# 11-DPLL-2.net
KiCad netlist of a schematic drawn in Altium Designer
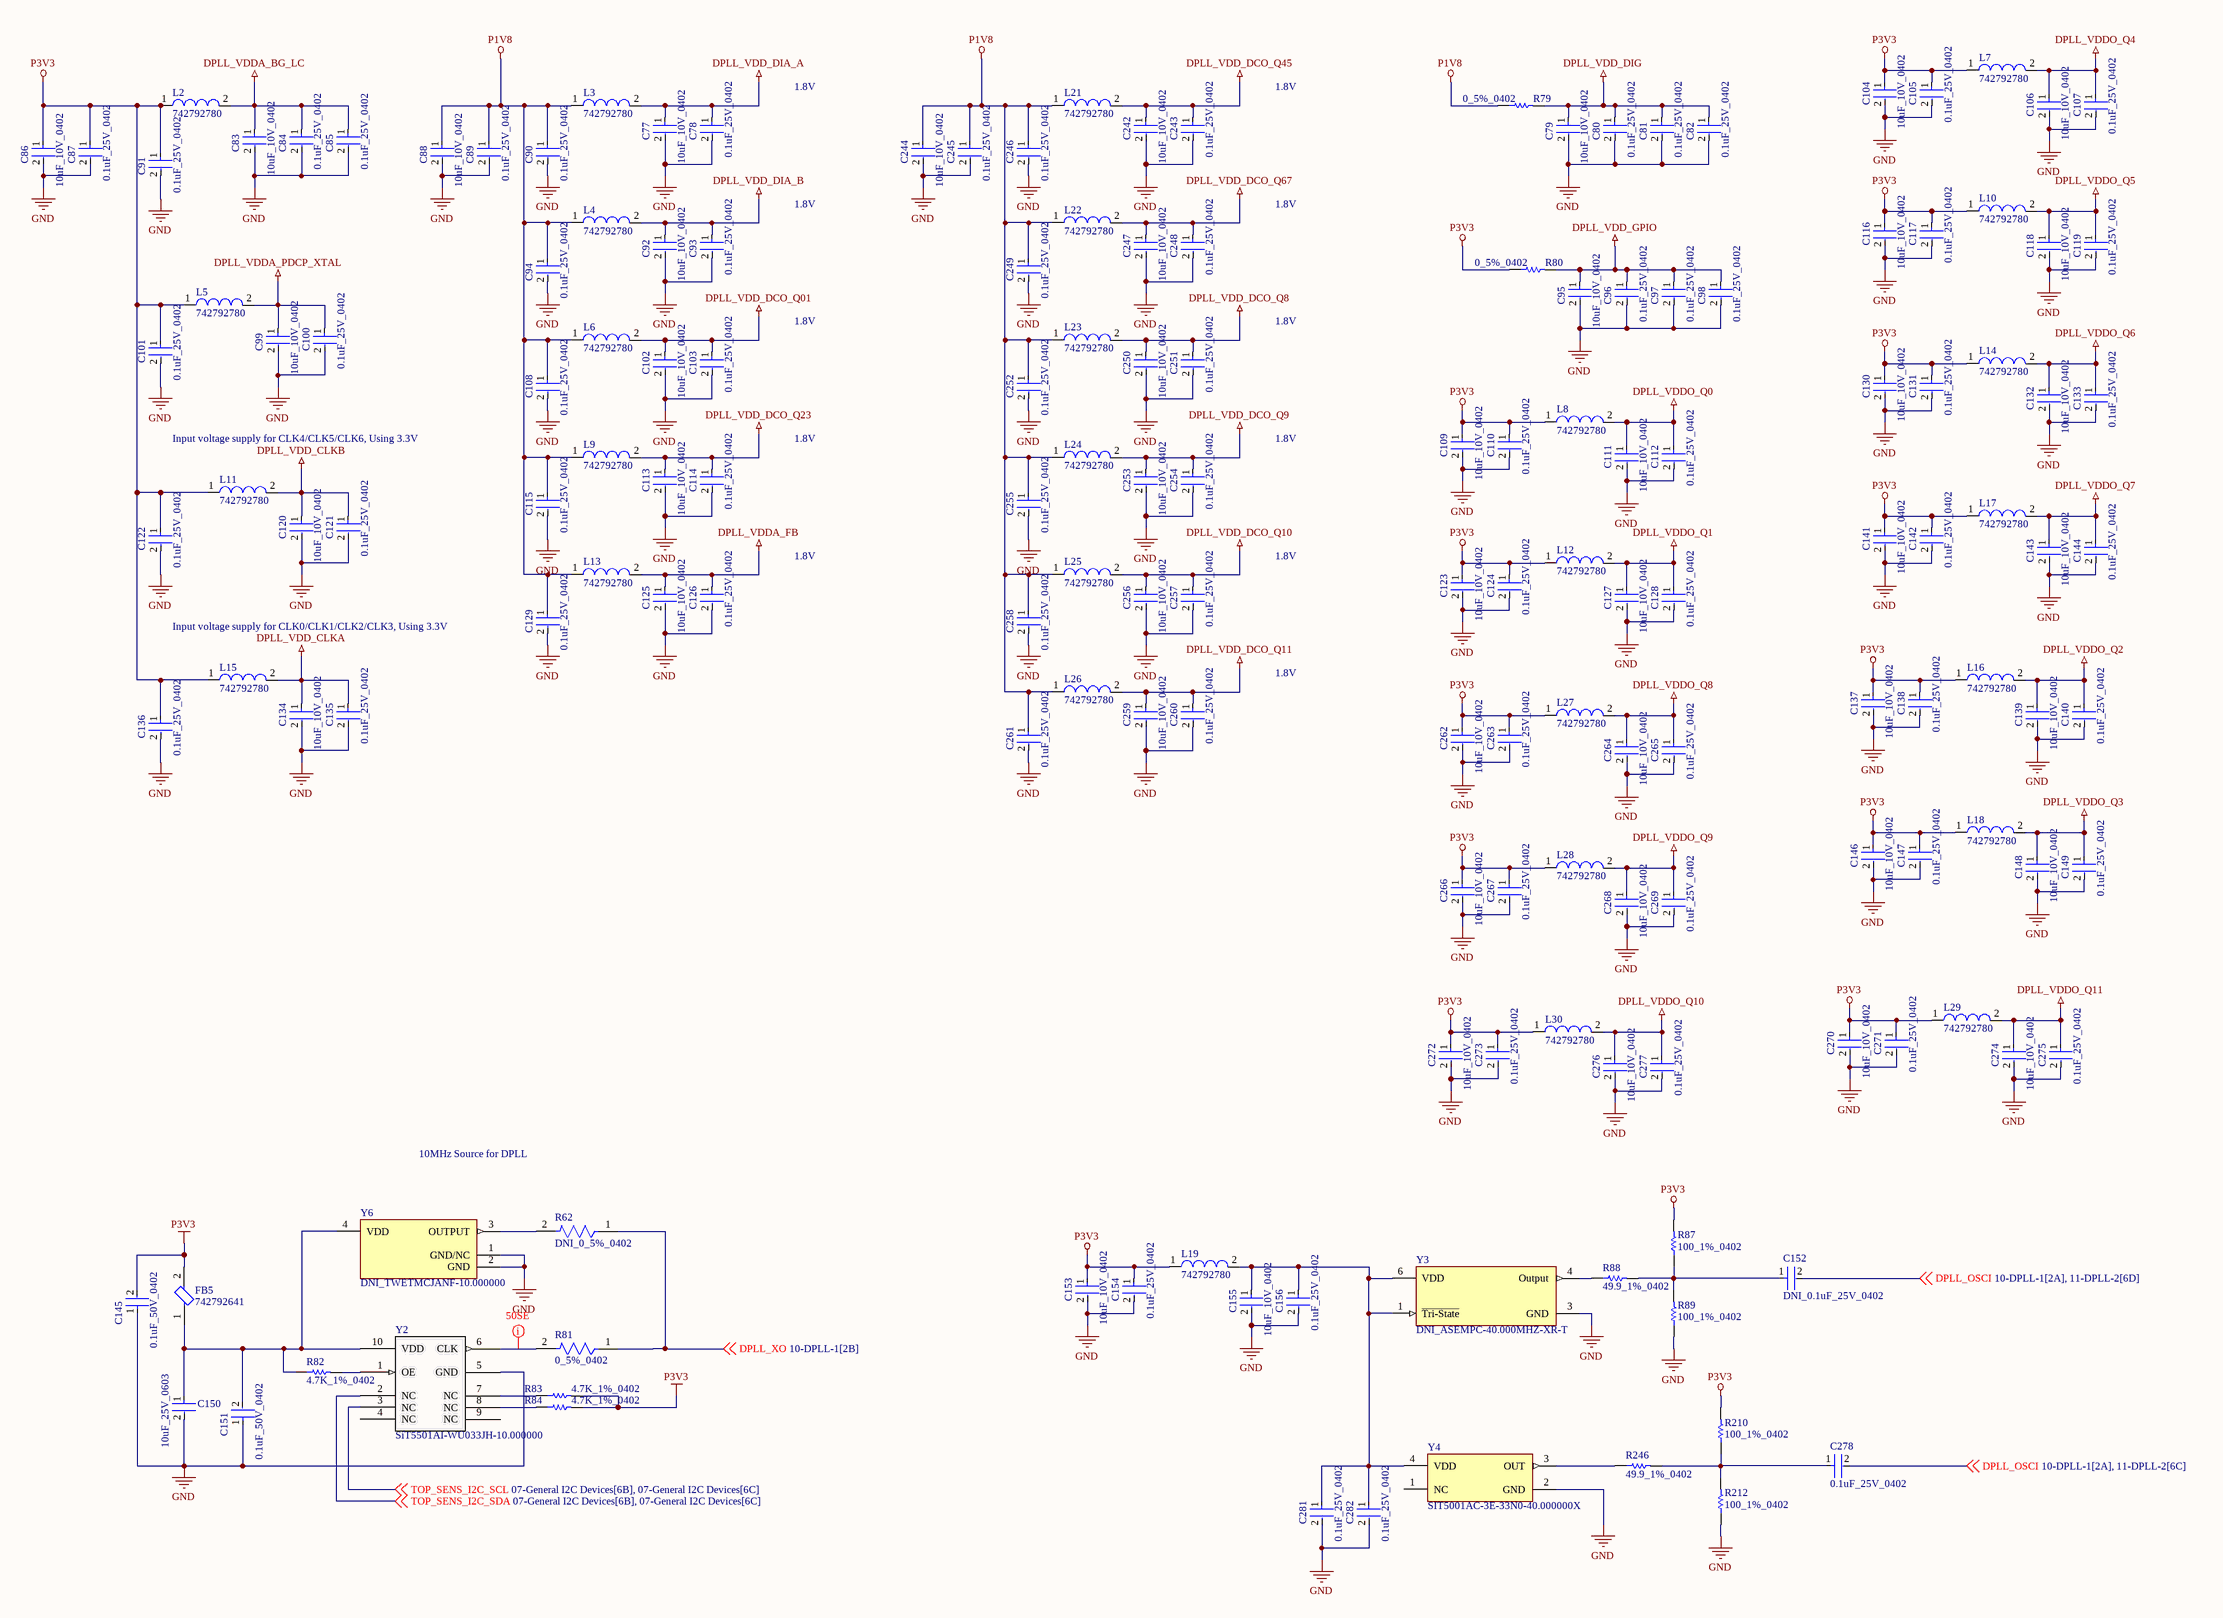
[diagram p0: 11-DPLL-2.SchDoc]

(export (version "E")
  (design (tool "Eeschema 10.0.6"))
  (components
    (comp (ref "C77")
      (value "10uF_10V_0402")
      (footprint "FP-CL05A106MP5NUNC-MFG")
      (description "CAP CER 10UF 10V X5R 0402")
      (fields
        (field (name "OCTOPART") "https://octopart.com/cl05a106mp5nunc-samsung-22457395")
        (field (name "TOLERANCE") "20%")
      )
      (libsource (lib "Altium Content Vault") (part "b4654b650e69147ec39a6b967a45e02"))
    )
    (comp (ref "C78")
      (value "0.1uF_25V_0402")
      (footprint "FP-0402-L_1_0_1-W_0_5_0_1-IPC_C")
      (description "General Purpose Ceramic Capacitor, 0402, 100nF, 10%, X7R, 15%, 25V")
      (fields (field (name "VOLTAGE") "25V") (field (name "TOLERANCE") "10%"))
      (libsource (lib "Altium Content Vault") (part "b4654b650e69147ec39a6b967a45e02"))
    )
    (comp (ref "C79")
      (value "10uF_10V_0402")
      (footprint "FP-CL05A106MP5NUNC-MFG")
      (description "CAP CER 10UF 10V X5R 0402")
      (fields
        (field (name "OCTOPART") "https://octopart.com/cl05a106mp5nunc-samsung-22457395")
        (field (name "TOLERANCE") "20%")
      )
      (libsource (lib "Altium Content Vault") (part "b4654b650e69147ec39a6b967a45e02"))
    )
    (comp (ref "C80")
      (value "0.1uF_25V_0402")
      (footprint "FP-0402-L_1_0_1-W_0_5_0_1-IPC_C")
      (description "General Purpose Ceramic Capacitor, 0402, 100nF, 10%, X7R, 15%, 25V")
      (fields (field (name "VOLTAGE") "25V") (field (name "TOLERANCE") "10%"))
      (libsource (lib "Altium Content Vault") (part "b4654b650e69147ec39a6b967a45e02"))
    )
    (comp (ref "C81")
      (value "0.1uF_25V_0402")
      (footprint "FP-0402-L_1_0_1-W_0_5_0_1-IPC_C")
      (description "General Purpose Ceramic Capacitor, 0402, 100nF, 10%, X7R, 15%, 25V")
      (fields (field (name "VOLTAGE") "25V") (field (name "TOLERANCE") "10%"))
      (libsource (lib "Altium Content Vault") (part "b4654b650e69147ec39a6b967a45e02"))
    )
    (comp (ref "C82")
      (value "0.1uF_25V_0402")
      (footprint "FP-0402-L_1_0_1-W_0_5_0_1-IPC_C")
      (description "General Purpose Ceramic Capacitor, 0402, 100nF, 10%, X7R, 15%, 25V")
      (fields (field (name "VOLTAGE") "25V") (field (name "TOLERANCE") "10%"))
      (libsource (lib "Altium Content Vault") (part "b4654b650e69147ec39a6b967a45e02"))
    )
    (comp (ref "C83")
      (value "10uF_10V_0402")
      (footprint "FP-CL05A106MP5NUNC-MFG")
      (description "CAP CER 10UF 10V X5R 0402")
      (fields
        (field (name "OCTOPART") "https://octopart.com/cl05a106mp5nunc-samsung-22457395")
        (field (name "TOLERANCE") "20%")
      )
      (libsource (lib "Altium Content Vault") (part "b4654b650e69147ec39a6b967a45e02"))
    )
    (comp (ref "C84")
      (value "0.1uF_25V_0402")
      (footprint "FP-0402-L_1_0_1-W_0_5_0_1-IPC_C")
      (description "General Purpose Ceramic Capacitor, 0402, 100nF, 10%, X7R, 15%, 25V")
      (fields (field (name "VOLTAGE") "25V") (field (name "TOLERANCE") "10%"))
      (libsource (lib "Altium Content Vault") (part "b4654b650e69147ec39a6b967a45e02"))
    )
    (comp (ref "C85")
      (value "0.1uF_25V_0402")
      (footprint "FP-0402-L_1_0_1-W_0_5_0_1-IPC_C")
      (description "General Purpose Ceramic Capacitor, 0402, 100nF, 10%, X7R, 15%, 25V")
      (fields (field (name "VOLTAGE") "25V") (field (name "TOLERANCE") "10%"))
      (libsource (lib "Altium Content Vault") (part "b4654b650e69147ec39a6b967a45e02"))
    )
    (comp (ref "C86")
      (value "10uF_10V_0402")
      (footprint "FP-CL05A106MP5NUNC-MFG")
      (description "CAP CER 10UF 10V X5R 0402")
      (fields
        (field (name "OCTOPART") "https://octopart.com/cl05a106mp5nunc-samsung-22457395")
        (field (name "TOLERANCE") "20%")
      )
      (libsource (lib "Altium Content Vault") (part "b4654b650e69147ec39a6b967a45e02"))
    )
    (comp (ref "C87")
      (value "0.1uF_25V_0402")
      (footprint "FP-0402-L_1_0_1-W_0_5_0_1-IPC_C")
      (description "General Purpose Ceramic Capacitor, 0402, 100nF, 10%, X7R, 15%, 25V")
      (fields (field (name "VOLTAGE") "25V") (field (name "TOLERANCE") "10%"))
      (libsource (lib "Altium Content Vault") (part "b4654b650e69147ec39a6b967a45e02"))
    )
    (comp (ref "C88")
      (value "10uF_10V_0402")
      (footprint "FP-CL05A106MP5NUNC-MFG")
      (description "CAP CER 10UF 10V X5R 0402")
      (fields
        (field (name "OCTOPART") "https://octopart.com/cl05a106mp5nunc-samsung-22457395")
        (field (name "TOLERANCE") "20%")
      )
      (libsource (lib "Altium Content Vault") (part "b4654b650e69147ec39a6b967a45e02"))
    )
    (comp (ref "C89")
      (value "0.1uF_25V_0402")
      (footprint "FP-0402-L_1_0_1-W_0_5_0_1-IPC_C")
      (description "General Purpose Ceramic Capacitor, 0402, 100nF, 10%, X7R, 15%, 25V")
      (fields (field (name "VOLTAGE") "25V") (field (name "TOLERANCE") "10%"))
      (libsource (lib "Altium Content Vault") (part "b4654b650e69147ec39a6b967a45e02"))
    )
    (comp (ref "C90")
      (value "0.1uF_25V_0402")
      (footprint "FP-0402-L_1_0_1-W_0_5_0_1-IPC_C")
      (description "General Purpose Ceramic Capacitor, 0402, 100nF, 10%, X7R, 15%, 25V")
      (fields (field (name "VOLTAGE") "25V") (field (name "TOLERANCE") "10%"))
      (libsource (lib "Altium Content Vault") (part "b4654b650e69147ec39a6b967a45e02"))
    )
    (comp (ref "C91")
      (value "0.1uF_25V_0402")
      (footprint "FP-0402-L_1_0_1-W_0_5_0_1-IPC_C")
      (description "General Purpose Ceramic Capacitor, 0402, 100nF, 10%, X7R, 15%, 25V")
      (fields (field (name "VOLTAGE") "25V") (field (name "TOLERANCE") "10%"))
      (libsource (lib "Altium Content Vault") (part "b4654b650e69147ec39a6b967a45e02"))
    )
    (comp (ref "C92")
      (value "10uF_10V_0402")
      (footprint "FP-CL05A106MP5NUNC-MFG")
      (description "CAP CER 10UF 10V X5R 0402")
      (fields
        (field (name "OCTOPART") "https://octopart.com/cl05a106mp5nunc-samsung-22457395")
        (field (name "TOLERANCE") "20%")
      )
      (libsource (lib "Altium Content Vault") (part "b4654b650e69147ec39a6b967a45e02"))
    )
    (comp (ref "C93")
      (value "0.1uF_25V_0402")
      (footprint "FP-0402-L_1_0_1-W_0_5_0_1-IPC_C")
      (description "General Purpose Ceramic Capacitor, 0402, 100nF, 10%, X7R, 15%, 25V")
      (fields (field (name "VOLTAGE") "25V") (field (name "TOLERANCE") "10%"))
      (libsource (lib "Altium Content Vault") (part "b4654b650e69147ec39a6b967a45e02"))
    )
    (comp (ref "C94")
      (value "0.1uF_25V_0402")
      (footprint "FP-0402-L_1_0_1-W_0_5_0_1-IPC_C")
      (description "General Purpose Ceramic Capacitor, 0402, 100nF, 10%, X7R, 15%, 25V")
      (fields (field (name "VOLTAGE") "25V") (field (name "TOLERANCE") "10%"))
      (libsource (lib "Altium Content Vault") (part "b4654b650e69147ec39a6b967a45e02"))
    )
    (comp (ref "C95")
      (value "10uF_10V_0402")
      (footprint "FP-CL05A106MP5NUNC-MFG")
      (description "CAP CER 10UF 10V X5R 0402")
      (fields
        (field (name "OCTOPART") "https://octopart.com/cl05a106mp5nunc-samsung-22457395")
        (field (name "TOLERANCE") "20%")
      )
      (libsource (lib "Altium Content Vault") (part "b4654b650e69147ec39a6b967a45e02"))
    )
    (comp (ref "C96")
      (value "0.1uF_25V_0402")
      (footprint "FP-0402-L_1_0_1-W_0_5_0_1-IPC_C")
      (description "General Purpose Ceramic Capacitor, 0402, 100nF, 10%, X7R, 15%, 25V")
      (fields (field (name "VOLTAGE") "25V") (field (name "TOLERANCE") "10%"))
      (libsource (lib "Altium Content Vault") (part "b4654b650e69147ec39a6b967a45e02"))
    )
    (comp (ref "C97")
      (value "0.1uF_25V_0402")
      (footprint "FP-0402-L_1_0_1-W_0_5_0_1-IPC_C")
      (description "General Purpose Ceramic Capacitor, 0402, 100nF, 10%, X7R, 15%, 25V")
      (fields (field (name "VOLTAGE") "25V") (field (name "TOLERANCE") "10%"))
      (libsource (lib "Altium Content Vault") (part "b4654b650e69147ec39a6b967a45e02"))
    )
    (comp (ref "C98")
      (value "0.1uF_25V_0402")
      (footprint "FP-0402-L_1_0_1-W_0_5_0_1-IPC_C")
      (description "General Purpose Ceramic Capacitor, 0402, 100nF, 10%, X7R, 15%, 25V")
      (fields (field (name "VOLTAGE") "25V") (field (name "TOLERANCE") "10%"))
      (libsource (lib "Altium Content Vault") (part "b4654b650e69147ec39a6b967a45e02"))
    )
    (comp (ref "C99")
      (value "10uF_10V_0402")
      (footprint "FP-CL05A106MP5NUNC-MFG")
      (description "CAP CER 10UF 10V X5R 0402")
      (fields
        (field (name "OCTOPART") "https://octopart.com/cl05a106mp5nunc-samsung-22457395")
        (field (name "TOLERANCE") "20%")
      )
      (libsource (lib "Altium Content Vault") (part "b4654b650e69147ec39a6b967a45e02"))
    )
    (comp (ref "C100")
      (value "0.1uF_25V_0402")
      (footprint "FP-0402-L_1_0_1-W_0_5_0_1-IPC_C")
      (description "General Purpose Ceramic Capacitor, 0402, 100nF, 10%, X7R, 15%, 25V")
      (fields (field (name "VOLTAGE") "25V") (field (name "TOLERANCE") "10%"))
      (libsource (lib "Altium Content Vault") (part "b4654b650e69147ec39a6b967a45e02"))
    )
    (comp (ref "C101")
      (value "0.1uF_25V_0402")
      (footprint "FP-0402-L_1_0_1-W_0_5_0_1-IPC_C")
      (description "General Purpose Ceramic Capacitor, 0402, 100nF, 10%, X7R, 15%, 25V")
      (fields (field (name "VOLTAGE") "25V") (field (name "TOLERANCE") "10%"))
      (libsource (lib "Altium Content Vault") (part "b4654b650e69147ec39a6b967a45e02"))
    )
    (comp (ref "C102")
      (value "10uF_10V_0402")
      (footprint "FP-CL05A106MP5NUNC-MFG")
      (description "CAP CER 10UF 10V X5R 0402")
      (fields
        (field (name "OCTOPART") "https://octopart.com/cl05a106mp5nunc-samsung-22457395")
        (field (name "TOLERANCE") "20%")
      )
      (libsource (lib "Altium Content Vault") (part "b4654b650e69147ec39a6b967a45e02"))
    )
    (comp (ref "C103")
      (value "0.1uF_25V_0402")
      (footprint "FP-0402-L_1_0_1-W_0_5_0_1-IPC_C")
      (description "General Purpose Ceramic Capacitor, 0402, 100nF, 10%, X7R, 15%, 25V")
      (fields (field (name "VOLTAGE") "25V") (field (name "TOLERANCE") "10%"))
      (libsource (lib "Altium Content Vault") (part "b4654b650e69147ec39a6b967a45e02"))
    )
    (comp (ref "C104")
      (value "10uF_10V_0402")
      (footprint "FP-CL05A106MP5NUNC-MFG")
      (description "CAP CER 10UF 10V X5R 0402")
      (fields
        (field (name "OCTOPART") "https://octopart.com/cl05a106mp5nunc-samsung-22457395")
        (field (name "TOLERANCE") "20%")
      )
      (libsource (lib "Altium Content Vault") (part "b4654b650e69147ec39a6b967a45e02"))
    )
    (comp (ref "C105")
      (value "0.1uF_25V_0402")
      (footprint "FP-0402-L_1_0_1-W_0_5_0_1-IPC_C")
      (description "General Purpose Ceramic Capacitor, 0402, 100nF, 10%, X7R, 15%, 25V")
      (fields (field (name "VOLTAGE") "25V") (field (name "TOLERANCE") "10%"))
      (libsource (lib "Altium Content Vault") (part "b4654b650e69147ec39a6b967a45e02"))
    )
    (comp (ref "C106")
      (value "10uF_10V_0402")
      (footprint "FP-CL05A106MP5NUNC-MFG")
      (description "CAP CER 10UF 10V X5R 0402")
      (fields
        (field (name "OCTOPART") "https://octopart.com/cl05a106mp5nunc-samsung-22457395")
        (field (name "TOLERANCE") "20%")
      )
      (libsource (lib "Altium Content Vault") (part "b4654b650e69147ec39a6b967a45e02"))
    )
    (comp (ref "C107")
      (value "0.1uF_25V_0402")
      (footprint "FP-0402-L_1_0_1-W_0_5_0_1-IPC_C")
      (description "General Purpose Ceramic Capacitor, 0402, 100nF, 10%, X7R, 15%, 25V")
      (fields (field (name "VOLTAGE") "25V") (field (name "TOLERANCE") "10%"))
      (libsource (lib "Altium Content Vault") (part "b4654b650e69147ec39a6b967a45e02"))
    )
    (comp (ref "C108")
      (value "0.1uF_25V_0402")
      (footprint "FP-0402-L_1_0_1-W_0_5_0_1-IPC_C")
      (description "General Purpose Ceramic Capacitor, 0402, 100nF, 10%, X7R, 15%, 25V")
      (fields (field (name "VOLTAGE") "25V") (field (name "TOLERANCE") "10%"))
      (libsource (lib "Altium Content Vault") (part "b4654b650e69147ec39a6b967a45e02"))
    )
    (comp (ref "C109")
      (value "10uF_10V_0402")
      (footprint "FP-CL05A106MP5NUNC-MFG")
      (description "CAP CER 10UF 10V X5R 0402")
      (fields
        (field (name "OCTOPART") "https://octopart.com/cl05a106mp5nunc-samsung-22457395")
        (field (name "TOLERANCE") "20%")
      )
      (libsource (lib "Altium Content Vault") (part "b4654b650e69147ec39a6b967a45e02"))
    )
    (comp (ref "C110")
      (value "0.1uF_25V_0402")
      (footprint "FP-0402-L_1_0_1-W_0_5_0_1-IPC_C")
      (description "General Purpose Ceramic Capacitor, 0402, 100nF, 10%, X7R, 15%, 25V")
      (fields (field (name "VOLTAGE") "25V") (field (name "TOLERANCE") "10%"))
      (libsource (lib "Altium Content Vault") (part "b4654b650e69147ec39a6b967a45e02"))
    )
    (comp (ref "C111")
      (value "10uF_10V_0402")
      (footprint "FP-CL05A106MP5NUNC-MFG")
      (description "CAP CER 10UF 10V X5R 0402")
      (fields
        (field (name "OCTOPART") "https://octopart.com/cl05a106mp5nunc-samsung-22457395")
        (field (name "TOLERANCE") "20%")
      )
      (libsource (lib "Altium Content Vault") (part "b4654b650e69147ec39a6b967a45e02"))
    )
    (comp (ref "C112")
      (value "0.1uF_25V_0402")
      (footprint "FP-0402-L_1_0_1-W_0_5_0_1-IPC_C")
      (description "General Purpose Ceramic Capacitor, 0402, 100nF, 10%, X7R, 15%, 25V")
      (fields (field (name "VOLTAGE") "25V") (field (name "TOLERANCE") "10%"))
      (libsource (lib "Altium Content Vault") (part "b4654b650e69147ec39a6b967a45e02"))
    )
    (comp (ref "C113")
      (value "10uF_10V_0402")
      (footprint "FP-CL05A106MP5NUNC-MFG")
      (description "CAP CER 10UF 10V X5R 0402")
      (fields
        (field (name "OCTOPART") "https://octopart.com/cl05a106mp5nunc-samsung-22457395")
        (field (name "TOLERANCE") "20%")
      )
      (libsource (lib "Altium Content Vault") (part "b4654b650e69147ec39a6b967a45e02"))
    )
    (comp (ref "C114")
      (value "0.1uF_25V_0402")
      (footprint "FP-0402-L_1_0_1-W_0_5_0_1-IPC_C")
      (description "General Purpose Ceramic Capacitor, 0402, 100nF, 10%, X7R, 15%, 25V")
      (fields (field (name "VOLTAGE") "25V") (field (name "TOLERANCE") "10%"))
      (libsource (lib "Altium Content Vault") (part "b4654b650e69147ec39a6b967a45e02"))
    )
    (comp (ref "C115")
      (value "0.1uF_25V_0402")
      (footprint "FP-0402-L_1_0_1-W_0_5_0_1-IPC_C")
      (description "General Purpose Ceramic Capacitor, 0402, 100nF, 10%, X7R, 15%, 25V")
      (fields (field (name "VOLTAGE") "25V") (field (name "TOLERANCE") "10%"))
      (libsource (lib "Altium Content Vault") (part "b4654b650e69147ec39a6b967a45e02"))
    )
    (comp (ref "C116")
      (value "10uF_10V_0402")
      (footprint "FP-CL05A106MP5NUNC-MFG")
      (description "CAP CER 10UF 10V X5R 0402")
      (fields
        (field (name "OCTOPART") "https://octopart.com/cl05a106mp5nunc-samsung-22457395")
        (field (name "TOLERANCE") "20%")
      )
      (libsource (lib "Altium Content Vault") (part "b4654b650e69147ec39a6b967a45e02"))
    )
    (comp (ref "C117")
      (value "0.1uF_25V_0402")
      (footprint "FP-0402-L_1_0_1-W_0_5_0_1-IPC_C")
      (description "General Purpose Ceramic Capacitor, 0402, 100nF, 10%, X7R, 15%, 25V")
      (fields (field (name "VOLTAGE") "25V") (field (name "TOLERANCE") "10%"))
      (libsource (lib "Altium Content Vault") (part "b4654b650e69147ec39a6b967a45e02"))
    )
    (comp (ref "C118")
      (value "10uF_10V_0402")
      (footprint "FP-CL05A106MP5NUNC-MFG")
      (description "CAP CER 10UF 10V X5R 0402")
      (fields
        (field (name "OCTOPART") "https://octopart.com/cl05a106mp5nunc-samsung-22457395")
        (field (name "TOLERANCE") "20%")
      )
      (libsource (lib "Altium Content Vault") (part "b4654b650e69147ec39a6b967a45e02"))
    )
    (comp (ref "C119")
      (value "0.1uF_25V_0402")
      (footprint "FP-0402-L_1_0_1-W_0_5_0_1-IPC_C")
      (description "General Purpose Ceramic Capacitor, 0402, 100nF, 10%, X7R, 15%, 25V")
      (fields (field (name "VOLTAGE") "25V") (field (name "TOLERANCE") "10%"))
      (libsource (lib "Altium Content Vault") (part "b4654b650e69147ec39a6b967a45e02"))
    )
    (comp (ref "C120")
      (value "10uF_10V_0402")
      (footprint "FP-CL05A106MP5NUNC-MFG")
      (description "CAP CER 10UF 10V X5R 0402")
      (fields
        (field (name "OCTOPART") "https://octopart.com/cl05a106mp5nunc-samsung-22457395")
        (field (name "TOLERANCE") "20%")
      )
      (libsource (lib "Altium Content Vault") (part "b4654b650e69147ec39a6b967a45e02"))
    )
    (comp (ref "C121")
      (value "0.1uF_25V_0402")
      (footprint "FP-0402-L_1_0_1-W_0_5_0_1-IPC_C")
      (description "General Purpose Ceramic Capacitor, 0402, 100nF, 10%, X7R, 15%, 25V")
      (fields (field (name "VOLTAGE") "25V") (field (name "TOLERANCE") "10%"))
      (libsource (lib "Altium Content Vault") (part "b4654b650e69147ec39a6b967a45e02"))
    )
    (comp (ref "C122")
      (value "0.1uF_25V_0402")
      (footprint "FP-0402-L_1_0_1-W_0_5_0_1-IPC_C")
      (description "General Purpose Ceramic Capacitor, 0402, 100nF, 10%, X7R, 15%, 25V")
      (fields (field (name "VOLTAGE") "25V") (field (name "TOLERANCE") "10%"))
      (libsource (lib "Altium Content Vault") (part "b4654b650e69147ec39a6b967a45e02"))
    )
    (comp (ref "C123")
      (value "10uF_10V_0402")
      (footprint "FP-CL05A106MP5NUNC-MFG")
      (description "CAP CER 10UF 10V X5R 0402")
      (fields
        (field (name "OCTOPART") "https://octopart.com/cl05a106mp5nunc-samsung-22457395")
        (field (name "TOLERANCE") "20%")
      )
      (libsource (lib "Altium Content Vault") (part "b4654b650e69147ec39a6b967a45e02"))
    )
    (comp (ref "C124")
      (value "0.1uF_25V_0402")
      (footprint "FP-0402-L_1_0_1-W_0_5_0_1-IPC_C")
      (description "General Purpose Ceramic Capacitor, 0402, 100nF, 10%, X7R, 15%, 25V")
      (fields (field (name "VOLTAGE") "25V") (field (name "TOLERANCE") "10%"))
      (libsource (lib "Altium Content Vault") (part "b4654b650e69147ec39a6b967a45e02"))
    )
    (comp (ref "C125")
      (value "10uF_10V_0402")
      (footprint "FP-CL05A106MP5NUNC-MFG")
      (description "CAP CER 10UF 10V X5R 0402")
      (fields
        (field (name "OCTOPART") "https://octopart.com/cl05a106mp5nunc-samsung-22457395")
        (field (name "TOLERANCE") "20%")
      )
      (libsource (lib "Altium Content Vault") (part "b4654b650e69147ec39a6b967a45e02"))
    )
    (comp (ref "C126")
      (value "0.1uF_25V_0402")
      (footprint "FP-0402-L_1_0_1-W_0_5_0_1-IPC_C")
      (description "General Purpose Ceramic Capacitor, 0402, 100nF, 10%, X7R, 15%, 25V")
      (fields (field (name "VOLTAGE") "25V") (field (name "TOLERANCE") "10%"))
      (libsource (lib "Altium Content Vault") (part "b4654b650e69147ec39a6b967a45e02"))
    )
    (comp (ref "C127")
      (value "10uF_10V_0402")
      (footprint "FP-CL05A106MP5NUNC-MFG")
      (description "CAP CER 10UF 10V X5R 0402")
      (fields
        (field (name "OCTOPART") "https://octopart.com/cl05a106mp5nunc-samsung-22457395")
        (field (name "TOLERANCE") "20%")
      )
      (libsource (lib "Altium Content Vault") (part "b4654b650e69147ec39a6b967a45e02"))
    )
    (comp (ref "C128")
      (value "0.1uF_25V_0402")
      (footprint "FP-0402-L_1_0_1-W_0_5_0_1-IPC_C")
      (description "General Purpose Ceramic Capacitor, 0402, 100nF, 10%, X7R, 15%, 25V")
      (fields (field (name "VOLTAGE") "25V") (field (name "TOLERANCE") "10%"))
      (libsource (lib "Altium Content Vault") (part "b4654b650e69147ec39a6b967a45e02"))
    )
    (comp (ref "C129")
      (value "0.1uF_25V_0402")
      (footprint "FP-0402-L_1_0_1-W_0_5_0_1-IPC_C")
      (description "General Purpose Ceramic Capacitor, 0402, 100nF, 10%, X7R, 15%, 25V")
      (fields (field (name "VOLTAGE") "25V") (field (name "TOLERANCE") "10%"))
      (libsource (lib "Altium Content Vault") (part "b4654b650e69147ec39a6b967a45e02"))
    )
    (comp (ref "C130")
      (value "10uF_10V_0402")
      (footprint "FP-CL05A106MP5NUNC-MFG")
      (description "CAP CER 10UF 10V X5R 0402")
      (fields
        (field (name "OCTOPART") "https://octopart.com/cl05a106mp5nunc-samsung-22457395")
        (field (name "TOLERANCE") "20%")
      )
      (libsource (lib "Altium Content Vault") (part "b4654b650e69147ec39a6b967a45e02"))
    )
    (comp (ref "C131")
      (value "0.1uF_25V_0402")
      (footprint "FP-0402-L_1_0_1-W_0_5_0_1-IPC_C")
      (description "General Purpose Ceramic Capacitor, 0402, 100nF, 10%, X7R, 15%, 25V")
      (fields (field (name "VOLTAGE") "25V") (field (name "TOLERANCE") "10%"))
      (libsource (lib "Altium Content Vault") (part "b4654b650e69147ec39a6b967a45e02"))
    )
    (comp (ref "C132")
      (value "10uF_10V_0402")
      (footprint "FP-CL05A106MP5NUNC-MFG")
      (description "CAP CER 10UF 10V X5R 0402")
      (fields
        (field (name "OCTOPART") "https://octopart.com/cl05a106mp5nunc-samsung-22457395")
        (field (name "TOLERANCE") "20%")
      )
      (libsource (lib "Altium Content Vault") (part "b4654b650e69147ec39a6b967a45e02"))
    )
    (comp (ref "C133")
      (value "0.1uF_25V_0402")
      (footprint "FP-0402-L_1_0_1-W_0_5_0_1-IPC_C")
      (description "General Purpose Ceramic Capacitor, 0402, 100nF, 10%, X7R, 15%, 25V")
      (fields (field (name "VOLTAGE") "25V") (field (name "TOLERANCE") "10%"))
      (libsource (lib "Altium Content Vault") (part "b4654b650e69147ec39a6b967a45e02"))
    )
    (comp (ref "C134")
      (value "10uF_10V_0402")
      (footprint "FP-CL05A106MP5NUNC-MFG")
      (description "CAP CER 10UF 10V X5R 0402")
      (fields
        (field (name "OCTOPART") "https://octopart.com/cl05a106mp5nunc-samsung-22457395")
        (field (name "TOLERANCE") "20%")
      )
      (libsource (lib "Altium Content Vault") (part "b4654b650e69147ec39a6b967a45e02"))
    )
    (comp (ref "C135")
      (value "0.1uF_25V_0402")
      (footprint "FP-0402-L_1_0_1-W_0_5_0_1-IPC_C")
      (description "General Purpose Ceramic Capacitor, 0402, 100nF, 10%, X7R, 15%, 25V")
      (fields (field (name "VOLTAGE") "25V") (field (name "TOLERANCE") "10%"))
      (libsource (lib "Altium Content Vault") (part "b4654b650e69147ec39a6b967a45e02"))
    )
    (comp (ref "C136")
      (value "0.1uF_25V_0402")
      (footprint "FP-0402-L_1_0_1-W_0_5_0_1-IPC_C")
      (description "General Purpose Ceramic Capacitor, 0402, 100nF, 10%, X7R, 15%, 25V")
      (fields (field (name "VOLTAGE") "25V") (field (name "TOLERANCE") "10%"))
      (libsource (lib "Altium Content Vault") (part "b4654b650e69147ec39a6b967a45e02"))
    )
    (comp (ref "C137")
      (value "10uF_10V_0402")
      (footprint "FP-CL05A106MP5NUNC-MFG")
      (description "CAP CER 10UF 10V X5R 0402")
      (fields
        (field (name "OCTOPART") "https://octopart.com/cl05a106mp5nunc-samsung-22457395")
        (field (name "TOLERANCE") "20%")
      )
      (libsource (lib "Altium Content Vault") (part "b4654b650e69147ec39a6b967a45e02"))
    )
    (comp (ref "C138")
      (value "0.1uF_25V_0402")
      (footprint "FP-0402-L_1_0_1-W_0_5_0_1-IPC_C")
      (description "General Purpose Ceramic Capacitor, 0402, 100nF, 10%, X7R, 15%, 25V")
      (fields (field (name "VOLTAGE") "25V") (field (name "TOLERANCE") "10%"))
      (libsource (lib "Altium Content Vault") (part "b4654b650e69147ec39a6b967a45e02"))
    )
    (comp (ref "C139")
      (value "10uF_10V_0402")
      (footprint "FP-CL05A106MP5NUNC-MFG")
      (description "CAP CER 10UF 10V X5R 0402")
      (fields
        (field (name "OCTOPART") "https://octopart.com/cl05a106mp5nunc-samsung-22457395")
        (field (name "TOLERANCE") "20%")
      )
      (libsource (lib "Altium Content Vault") (part "b4654b650e69147ec39a6b967a45e02"))
    )
    (comp (ref "C140")
      (value "0.1uF_25V_0402")
      (footprint "FP-0402-L_1_0_1-W_0_5_0_1-IPC_C")
      (description "General Purpose Ceramic Capacitor, 0402, 100nF, 10%, X7R, 15%, 25V")
      (fields (field (name "VOLTAGE") "25V") (field (name "TOLERANCE") "10%"))
      (libsource (lib "Altium Content Vault") (part "b4654b650e69147ec39a6b967a45e02"))
    )
    (comp (ref "C141")
      (value "10uF_10V_0402")
      (footprint "FP-CL05A106MP5NUNC-MFG")
      (description "CAP CER 10UF 10V X5R 0402")
      (fields
        (field (name "OCTOPART") "https://octopart.com/cl05a106mp5nunc-samsung-22457395")
        (field (name "TOLERANCE") "20%")
      )
      (libsource (lib "Altium Content Vault") (part "b4654b650e69147ec39a6b967a45e02"))
    )
    (comp (ref "C142")
      (value "0.1uF_25V_0402")
      (footprint "FP-0402-L_1_0_1-W_0_5_0_1-IPC_C")
      (description "General Purpose Ceramic Capacitor, 0402, 100nF, 10%, X7R, 15%, 25V")
      (fields (field (name "VOLTAGE") "25V") (field (name "TOLERANCE") "10%"))
      (libsource (lib "Altium Content Vault") (part "b4654b650e69147ec39a6b967a45e02"))
    )
    (comp (ref "C143")
      (value "10uF_10V_0402")
      (footprint "FP-CL05A106MP5NUNC-MFG")
      (description "CAP CER 10UF 10V X5R 0402")
      (fields
        (field (name "OCTOPART") "https://octopart.com/cl05a106mp5nunc-samsung-22457395")
        (field (name "TOLERANCE") "20%")
      )
      (libsource (lib "Altium Content Vault") (part "b4654b650e69147ec39a6b967a45e02"))
    )
    (comp (ref "C144")
      (value "0.1uF_25V_0402")
      (footprint "FP-0402-L_1_0_1-W_0_5_0_1-IPC_C")
      (description "General Purpose Ceramic Capacitor, 0402, 100nF, 10%, X7R, 15%, 25V")
      (fields (field (name "VOLTAGE") "25V") (field (name "TOLERANCE") "10%"))
      (libsource (lib "Altium Content Vault") (part "b4654b650e69147ec39a6b967a45e02"))
    )
    (comp (ref "C145")
      (value "0.1uF_50V_0402")
      (footprint "FP-C1005-050-0_05-IPC_C")
      (description "Multilayer Ceramic Capacitors 100nF ±10% 50V X7R SMD 0402")
      (fields (field (name "VOLTAGE") "50V") (field (name "TOLERANCE") "10%"))
      (libsource (lib "Altium Content Vault") (part "b4654b650e69147ec39a6b967a45e02"))
    )
    (comp (ref "C146")
      (value "10uF_10V_0402")
      (footprint "FP-CL05A106MP5NUNC-MFG")
      (description "CAP CER 10UF 10V X5R 0402")
      (fields
        (field (name "OCTOPART") "https://octopart.com/cl05a106mp5nunc-samsung-22457395")
        (field (name "TOLERANCE") "20%")
      )
      (libsource (lib "Altium Content Vault") (part "b4654b650e69147ec39a6b967a45e02"))
    )
    (comp (ref "C147")
      (value "0.1uF_25V_0402")
      (footprint "FP-0402-L_1_0_1-W_0_5_0_1-IPC_C")
      (description "General Purpose Ceramic Capacitor, 0402, 100nF, 10%, X7R, 15%, 25V")
      (fields (field (name "VOLTAGE") "25V") (field (name "TOLERANCE") "10%"))
      (libsource (lib "Altium Content Vault") (part "b4654b650e69147ec39a6b967a45e02"))
    )
    (comp (ref "C148")
      (value "10uF_10V_0402")
      (footprint "FP-CL05A106MP5NUNC-MFG")
      (description "CAP CER 10UF 10V X5R 0402")
      (fields
        (field (name "OCTOPART") "https://octopart.com/cl05a106mp5nunc-samsung-22457395")
        (field (name "TOLERANCE") "20%")
      )
      (libsource (lib "Altium Content Vault") (part "b4654b650e69147ec39a6b967a45e02"))
    )
    (comp (ref "C149")
      (value "0.1uF_25V_0402")
      (footprint "FP-0402-L_1_0_1-W_0_5_0_1-IPC_C")
      (description "General Purpose Ceramic Capacitor, 0402, 100nF, 10%, X7R, 15%, 25V")
      (fields (field (name "VOLTAGE") "25V") (field (name "TOLERANCE") "10%"))
      (libsource (lib "Altium Content Vault") (part "b4654b650e69147ec39a6b967a45e02"))
    )
    (comp (ref "C150")
      (value "10uF_25V_0603")
      (footprint "FP-CL10-IPC_C")
      (description "Cap Ceramic 10uF 25V X5R ±20% Pad SMD 0603 +85°C T/R")
      (fields (field (name "TOLERANCE") "20%"))
      (libsource (lib "Altium Content Vault") (part "b4654b650e69147ec39a6b967a45e02"))
    )
    (comp (ref "C151")
      (value "0.1uF_50V_0402")
      (footprint "FP-C1005-050-0_05-IPC_C")
      (description "Multilayer Ceramic Capacitors 100nF ±10% 50V X7R SMD 0402")
      (fields (field (name "VOLTAGE") "50V") (field (name "TOLERANCE") "10%"))
      (libsource (lib "Altium Content Vault") (part "b4654b650e69147ec39a6b967a45e02"))
    )
    (comp (ref "C152")
      (value "DNI_0.1uF_25V_0402")
      (footprint "FP-0402-L_1_0_1-W_0_5_0_1-IPC_C")
      (description "General Purpose Ceramic Capacitor, 0402, 100nF, 10%, X7R, 15%, 25V")
      (fields (field (name "VOLTAGE") "25V") (field (name "TOLERANCE") "10%"))
      (libsource (lib "Altium Content Vault") (part "b4654b650e69147ec39a6b967a45e02"))
    )
    (comp (ref "C153")
      (value "10uF_10V_0402")
      (footprint "FP-CL05A106MP5NUNC-MFG")
      (description "CAP CER 10UF 10V X5R 0402")
      (fields
        (field (name "OCTOPART") "https://octopart.com/cl05a106mp5nunc-samsung-22457395")
        (field (name "TOLERANCE") "20%")
      )
      (libsource (lib "Altium Content Vault") (part "b4654b650e69147ec39a6b967a45e02"))
    )
    (comp (ref "C154")
      (value "0.1uF_25V_0402")
      (footprint "FP-0402-L_1_0_1-W_0_5_0_1-IPC_C")
      (description "General Purpose Ceramic Capacitor, 0402, 100nF, 10%, X7R, 15%, 25V")
      (fields (field (name "VOLTAGE") "25V") (field (name "TOLERANCE") "10%"))
      (libsource (lib "Altium Content Vault") (part "b4654b650e69147ec39a6b967a45e02"))
    )
    (comp (ref "C155")
      (value "10uF_10V_0402")
      (footprint "FP-CL05A106MP5NUNC-MFG")
      (description "CAP CER 10UF 10V X5R 0402")
      (fields
        (field (name "OCTOPART") "https://octopart.com/cl05a106mp5nunc-samsung-22457395")
        (field (name "TOLERANCE") "20%")
      )
      (libsource (lib "Altium Content Vault") (part "b4654b650e69147ec39a6b967a45e02"))
    )
    (comp (ref "C156")
      (value "0.1uF_25V_0402")
      (footprint "FP-0402-L_1_0_1-W_0_5_0_1-IPC_C")
      (description "General Purpose Ceramic Capacitor, 0402, 100nF, 10%, X7R, 15%, 25V")
      (fields (field (name "VOLTAGE") "25V") (field (name "TOLERANCE") "10%"))
      (libsource (lib "Altium Content Vault") (part "b4654b650e69147ec39a6b967a45e02"))
    )
    (comp (ref "C242")
      (value "10uF_10V_0402")
      (footprint "FP-CL05A106MP5NUNC-MFG")
      (description "CAP CER 10UF 10V X5R 0402")
      (fields
        (field (name "OCTOPART") "https://octopart.com/cl05a106mp5nunc-samsung-22457395")
        (field (name "TOLERANCE") "20%")
      )
      (libsource (lib "Altium Content Vault") (part "b4654b650e69147ec39a6b967a45e02"))
    )
    (comp (ref "C243")
      (value "0.1uF_25V_0402")
      (footprint "FP-0402-L_1_0_1-W_0_5_0_1-IPC_C")
      (description "General Purpose Ceramic Capacitor, 0402, 100nF, 10%, X7R, 15%, 25V")
      (fields (field (name "VOLTAGE") "25V") (field (name "TOLERANCE") "10%"))
      (libsource (lib "Altium Content Vault") (part "b4654b650e69147ec39a6b967a45e02"))
    )
    (comp (ref "C244")
      (value "10uF_10V_0402")
      (footprint "FP-CL05A106MP5NUNC-MFG")
      (description "CAP CER 10UF 10V X5R 0402")
      (fields
        (field (name "OCTOPART") "https://octopart.com/cl05a106mp5nunc-samsung-22457395")
        (field (name "TOLERANCE") "20%")
      )
      (libsource (lib "Altium Content Vault") (part "b4654b650e69147ec39a6b967a45e02"))
    )
    (comp (ref "C245")
      (value "0.1uF_25V_0402")
      (footprint "FP-0402-L_1_0_1-W_0_5_0_1-IPC_C")
      (description "General Purpose Ceramic Capacitor, 0402, 100nF, 10%, X7R, 15%, 25V")
      (fields (field (name "VOLTAGE") "25V") (field (name "TOLERANCE") "10%"))
      (libsource (lib "Altium Content Vault") (part "b4654b650e69147ec39a6b967a45e02"))
    )
    (comp (ref "C246")
      (value "0.1uF_25V_0402")
      (footprint "FP-0402-L_1_0_1-W_0_5_0_1-IPC_C")
      (description "General Purpose Ceramic Capacitor, 0402, 100nF, 10%, X7R, 15%, 25V")
      (fields (field (name "VOLTAGE") "25V") (field (name "TOLERANCE") "10%"))
      (libsource (lib "Altium Content Vault") (part "b4654b650e69147ec39a6b967a45e02"))
    )
    (comp (ref "C247")
      (value "10uF_10V_0402")
      (footprint "FP-CL05A106MP5NUNC-MFG")
      (description "CAP CER 10UF 10V X5R 0402")
      (fields
        (field (name "OCTOPART") "https://octopart.com/cl05a106mp5nunc-samsung-22457395")
        (field (name "TOLERANCE") "20%")
      )
      (libsource (lib "Altium Content Vault") (part "b4654b650e69147ec39a6b967a45e02"))
    )
    (comp (ref "C248")
      (value "0.1uF_25V_0402")
      (footprint "FP-0402-L_1_0_1-W_0_5_0_1-IPC_C")
      (description "General Purpose Ceramic Capacitor, 0402, 100nF, 10%, X7R, 15%, 25V")
      (fields (field (name "VOLTAGE") "25V") (field (name "TOLERANCE") "10%"))
      (libsource (lib "Altium Content Vault") (part "b4654b650e69147ec39a6b967a45e02"))
    )
    (comp (ref "C249")
      (value "0.1uF_25V_0402")
      (footprint "FP-0402-L_1_0_1-W_0_5_0_1-IPC_C")
      (description "General Purpose Ceramic Capacitor, 0402, 100nF, 10%, X7R, 15%, 25V")
      (fields (field (name "VOLTAGE") "25V") (field (name "TOLERANCE") "10%"))
      (libsource (lib "Altium Content Vault") (part "b4654b650e69147ec39a6b967a45e02"))
    )
    (comp (ref "C250")
      (value "10uF_10V_0402")
      (footprint "FP-CL05A106MP5NUNC-MFG")
      (description "CAP CER 10UF 10V X5R 0402")
      (fields
        (field (name "OCTOPART") "https://octopart.com/cl05a106mp5nunc-samsung-22457395")
        (field (name "TOLERANCE") "20%")
      )
      (libsource (lib "Altium Content Vault") (part "b4654b650e69147ec39a6b967a45e02"))
    )
    (comp (ref "C251")
      (value "0.1uF_25V_0402")
      (footprint "FP-0402-L_1_0_1-W_0_5_0_1-IPC_C")
      (description "General Purpose Ceramic Capacitor, 0402, 100nF, 10%, X7R, 15%, 25V")
      (fields (field (name "VOLTAGE") "25V") (field (name "TOLERANCE") "10%"))
      (libsource (lib "Altium Content Vault") (part "b4654b650e69147ec39a6b967a45e02"))
    )
    (comp (ref "C252")
      (value "0.1uF_25V_0402")
      (footprint "FP-0402-L_1_0_1-W_0_5_0_1-IPC_C")
      (description "General Purpose Ceramic Capacitor, 0402, 100nF, 10%, X7R, 15%, 25V")
      (fields (field (name "VOLTAGE") "25V") (field (name "TOLERANCE") "10%"))
      (libsource (lib "Altium Content Vault") (part "b4654b650e69147ec39a6b967a45e02"))
    )
    (comp (ref "C253")
      (value "10uF_10V_0402")
      (footprint "FP-CL05A106MP5NUNC-MFG")
      (description "CAP CER 10UF 10V X5R 0402")
      (fields
        (field (name "OCTOPART") "https://octopart.com/cl05a106mp5nunc-samsung-22457395")
        (field (name "TOLERANCE") "20%")
      )
      (libsource (lib "Altium Content Vault") (part "b4654b650e69147ec39a6b967a45e02"))
    )
    (comp (ref "C254")
      (value "0.1uF_25V_0402")
      (footprint "FP-0402-L_1_0_1-W_0_5_0_1-IPC_C")
      (description "General Purpose Ceramic Capacitor, 0402, 100nF, 10%, X7R, 15%, 25V")
      (fields (field (name "VOLTAGE") "25V") (field (name "TOLERANCE") "10%"))
      (libsource (lib "Altium Content Vault") (part "b4654b650e69147ec39a6b967a45e02"))
    )
    (comp (ref "C255")
      (value "0.1uF_25V_0402")
      (footprint "FP-0402-L_1_0_1-W_0_5_0_1-IPC_C")
      (description "General Purpose Ceramic Capacitor, 0402, 100nF, 10%, X7R, 15%, 25V")
      (fields (field (name "VOLTAGE") "25V") (field (name "TOLERANCE") "10%"))
      (libsource (lib "Altium Content Vault") (part "b4654b650e69147ec39a6b967a45e02"))
    )
    (comp (ref "C256")
      (value "10uF_10V_0402")
      (footprint "FP-CL05A106MP5NUNC-MFG")
      (description "CAP CER 10UF 10V X5R 0402")
      (fields
        (field (name "OCTOPART") "https://octopart.com/cl05a106mp5nunc-samsung-22457395")
        (field (name "TOLERANCE") "20%")
      )
      (libsource (lib "Altium Content Vault") (part "b4654b650e69147ec39a6b967a45e02"))
    )
    (comp (ref "C257")
      (value "0.1uF_25V_0402")
      (footprint "FP-0402-L_1_0_1-W_0_5_0_1-IPC_C")
      (description "General Purpose Ceramic Capacitor, 0402, 100nF, 10%, X7R, 15%, 25V")
      (fields (field (name "VOLTAGE") "25V") (field (name "TOLERANCE") "10%"))
      (libsource (lib "Altium Content Vault") (part "b4654b650e69147ec39a6b967a45e02"))
    )
    (comp (ref "C258")
      (value "0.1uF_25V_0402")
      (footprint "FP-0402-L_1_0_1-W_0_5_0_1-IPC_C")
      (description "General Purpose Ceramic Capacitor, 0402, 100nF, 10%, X7R, 15%, 25V")
      (fields (field (name "VOLTAGE") "25V") (field (name "TOLERANCE") "10%"))
      (libsource (lib "Altium Content Vault") (part "b4654b650e69147ec39a6b967a45e02"))
    )
    (comp (ref "C259")
      (value "10uF_10V_0402")
      (footprint "FP-CL05A106MP5NUNC-MFG")
      (description "CAP CER 10UF 10V X5R 0402")
      (fields
        (field (name "OCTOPART") "https://octopart.com/cl05a106mp5nunc-samsung-22457395")
        (field (name "TOLERANCE") "20%")
      )
      (libsource (lib "Altium Content Vault") (part "b4654b650e69147ec39a6b967a45e02"))
    )
    (comp (ref "C260")
      (value "0.1uF_25V_0402")
      (footprint "FP-0402-L_1_0_1-W_0_5_0_1-IPC_C")
      (description "General Purpose Ceramic Capacitor, 0402, 100nF, 10%, X7R, 15%, 25V")
      (fields (field (name "VOLTAGE") "25V") (field (name "TOLERANCE") "10%"))
      (libsource (lib "Altium Content Vault") (part "b4654b650e69147ec39a6b967a45e02"))
    )
    (comp (ref "C261")
      (value "0.1uF_25V_0402")
      (footprint "FP-0402-L_1_0_1-W_0_5_0_1-IPC_C")
      (description "General Purpose Ceramic Capacitor, 0402, 100nF, 10%, X7R, 15%, 25V")
      (fields (field (name "VOLTAGE") "25V") (field (name "TOLERANCE") "10%"))
      (libsource (lib "Altium Content Vault") (part "b4654b650e69147ec39a6b967a45e02"))
    )
    (comp (ref "C262")
      (value "10uF_10V_0402")
      (footprint "FP-CL05A106MP5NUNC-MFG")
      (description "CAP CER 10UF 10V X5R 0402")
      (fields
        (field (name "OCTOPART") "https://octopart.com/cl05a106mp5nunc-samsung-22457395")
        (field (name "TOLERANCE") "20%")
      )
      (libsource (lib "Altium Content Vault") (part "b4654b650e69147ec39a6b967a45e02"))
    )
    (comp (ref "C263")
      (value "0.1uF_25V_0402")
      (footprint "FP-0402-L_1_0_1-W_0_5_0_1-IPC_C")
      (description "General Purpose Ceramic Capacitor, 0402, 100nF, 10%, X7R, 15%, 25V")
      (fields (field (name "VOLTAGE") "25V") (field (name "TOLERANCE") "10%"))
      (libsource (lib "Altium Content Vault") (part "b4654b650e69147ec39a6b967a45e02"))
    )
    (comp (ref "C264")
      (value "10uF_10V_0402")
      (footprint "FP-CL05A106MP5NUNC-MFG")
      (description "CAP CER 10UF 10V X5R 0402")
      (fields
        (field (name "OCTOPART") "https://octopart.com/cl05a106mp5nunc-samsung-22457395")
        (field (name "TOLERANCE") "20%")
      )
      (libsource (lib "Altium Content Vault") (part "b4654b650e69147ec39a6b967a45e02"))
    )
    (comp (ref "C265")
      (value "0.1uF_25V_0402")
      (footprint "FP-0402-L_1_0_1-W_0_5_0_1-IPC_C")
      (description "General Purpose Ceramic Capacitor, 0402, 100nF, 10%, X7R, 15%, 25V")
      (fields (field (name "VOLTAGE") "25V") (field (name "TOLERANCE") "10%"))
      (libsource (lib "Altium Content Vault") (part "b4654b650e69147ec39a6b967a45e02"))
    )
    (comp (ref "C266")
      (value "10uF_10V_0402")
      (footprint "FP-CL05A106MP5NUNC-MFG")
      (description "CAP CER 10UF 10V X5R 0402")
      (fields
        (field (name "OCTOPART") "https://octopart.com/cl05a106mp5nunc-samsung-22457395")
        (field (name "TOLERANCE") "20%")
      )
      (libsource (lib "Altium Content Vault") (part "b4654b650e69147ec39a6b967a45e02"))
    )
    (comp (ref "C267")
      (value "0.1uF_25V_0402")
      (footprint "FP-0402-L_1_0_1-W_0_5_0_1-IPC_C")
      (description "General Purpose Ceramic Capacitor, 0402, 100nF, 10%, X7R, 15%, 25V")
      (fields (field (name "VOLTAGE") "25V") (field (name "TOLERANCE") "10%"))
      (libsource (lib "Altium Content Vault") (part "b4654b650e69147ec39a6b967a45e02"))
    )
    (comp (ref "C268")
      (value "10uF_10V_0402")
      (footprint "FP-CL05A106MP5NUNC-MFG")
      (description "CAP CER 10UF 10V X5R 0402")
      (fields
        (field (name "OCTOPART") "https://octopart.com/cl05a106mp5nunc-samsung-22457395")
        (field (name "TOLERANCE") "20%")
      )
      (libsource (lib "Altium Content Vault") (part "b4654b650e69147ec39a6b967a45e02"))
    )
    (comp (ref "C269")
      (value "0.1uF_25V_0402")
      (footprint "FP-0402-L_1_0_1-W_0_5_0_1-IPC_C")
      (description "General Purpose Ceramic Capacitor, 0402, 100nF, 10%, X7R, 15%, 25V")
      (fields (field (name "VOLTAGE") "25V") (field (name "TOLERANCE") "10%"))
      (libsource (lib "Altium Content Vault") (part "b4654b650e69147ec39a6b967a45e02"))
    )
    (comp (ref "C270")
      (value "10uF_10V_0402")
      (footprint "FP-CL05A106MP5NUNC-MFG")
      (description "CAP CER 10UF 10V X5R 0402")
      (fields
        (field (name "OCTOPART") "https://octopart.com/cl05a106mp5nunc-samsung-22457395")
        (field (name "TOLERANCE") "20%")
      )
      (libsource (lib "Altium Content Vault") (part "b4654b650e69147ec39a6b967a45e02"))
    )
    (comp (ref "C271")
      (value "0.1uF_25V_0402")
      (footprint "FP-0402-L_1_0_1-W_0_5_0_1-IPC_C")
      (description "General Purpose Ceramic Capacitor, 0402, 100nF, 10%, X7R, 15%, 25V")
      (fields (field (name "VOLTAGE") "25V") (field (name "TOLERANCE") "10%"))
      (libsource (lib "Altium Content Vault") (part "b4654b650e69147ec39a6b967a45e02"))
    )
    (comp (ref "C272")
      (value "10uF_10V_0402")
      (footprint "FP-CL05A106MP5NUNC-MFG")
      (description "CAP CER 10UF 10V X5R 0402")
      (fields
        (field (name "OCTOPART") "https://octopart.com/cl05a106mp5nunc-samsung-22457395")
        (field (name "TOLERANCE") "20%")
      )
      (libsource (lib "Altium Content Vault") (part "b4654b650e69147ec39a6b967a45e02"))
    )
    (comp (ref "C273")
      (value "0.1uF_25V_0402")
      (footprint "FP-0402-L_1_0_1-W_0_5_0_1-IPC_C")
      (description "General Purpose Ceramic Capacitor, 0402, 100nF, 10%, X7R, 15%, 25V")
      (fields (field (name "VOLTAGE") "25V") (field (name "TOLERANCE") "10%"))
      (libsource (lib "Altium Content Vault") (part "b4654b650e69147ec39a6b967a45e02"))
    )
    (comp (ref "C274")
      (value "10uF_10V_0402")
      (footprint "FP-CL05A106MP5NUNC-MFG")
      (description "CAP CER 10UF 10V X5R 0402")
      (fields
        (field (name "OCTOPART") "https://octopart.com/cl05a106mp5nunc-samsung-22457395")
        (field (name "TOLERANCE") "20%")
      )
      (libsource (lib "Altium Content Vault") (part "b4654b650e69147ec39a6b967a45e02"))
    )
    (comp (ref "C275")
      (value "0.1uF_25V_0402")
      (footprint "FP-0402-L_1_0_1-W_0_5_0_1-IPC_C")
      (description "General Purpose Ceramic Capacitor, 0402, 100nF, 10%, X7R, 15%, 25V")
      (fields (field (name "VOLTAGE") "25V") (field (name "TOLERANCE") "10%"))
      (libsource (lib "Altium Content Vault") (part "b4654b650e69147ec39a6b967a45e02"))
    )
    (comp (ref "C276")
      (value "10uF_10V_0402")
      (footprint "FP-CL05A106MP5NUNC-MFG")
      (description "CAP CER 10UF 10V X5R 0402")
      (fields
        (field (name "OCTOPART") "https://octopart.com/cl05a106mp5nunc-samsung-22457395")
        (field (name "TOLERANCE") "20%")
      )
      (libsource (lib "Altium Content Vault") (part "b4654b650e69147ec39a6b967a45e02"))
    )
    (comp (ref "C277")
      (value "0.1uF_25V_0402")
      (footprint "FP-0402-L_1_0_1-W_0_5_0_1-IPC_C")
      (description "General Purpose Ceramic Capacitor, 0402, 100nF, 10%, X7R, 15%, 25V")
      (fields (field (name "VOLTAGE") "25V") (field (name "TOLERANCE") "10%"))
      (libsource (lib "Altium Content Vault") (part "b4654b650e69147ec39a6b967a45e02"))
    )
    (comp (ref "C278")
      (value "0.1uF_25V_0402")
      (footprint "FP-0402-L_1_0_1-W_0_5_0_1-IPC_C")
      (description "General Purpose Ceramic Capacitor, 0402, 100nF, 10%, X7R, 15%, 25V")
      (fields (field (name "VOLTAGE") "25V") (field (name "TOLERANCE") "10%"))
      (libsource (lib "Altium Content Vault") (part "b4654b650e69147ec39a6b967a45e02"))
    )
    (comp (ref "C281")
      (value "0.1uF_25V_0402")
      (footprint "FP-0402-L_1_0_1-W_0_5_0_1-IPC_C")
      (description "General Purpose Ceramic Capacitor, 0402, 100nF, 10%, X7R, 15%, 25V")
      (fields (field (name "VOLTAGE") "25V") (field (name "TOLERANCE") "10%"))
      (libsource (lib "Altium Content Vault") (part "b4654b650e69147ec39a6b967a45e02"))
    )
    (comp (ref "C282")
      (value "0.1uF_25V_0402")
      (footprint "FP-0402-L_1_0_1-W_0_5_0_1-IPC_C")
      (description "General Purpose Ceramic Capacitor, 0402, 100nF, 10%, X7R, 15%, 25V")
      (fields (field (name "VOLTAGE") "25V") (field (name "TOLERANCE") "10%"))
      (libsource (lib "Altium Content Vault") (part "b4654b650e69147ec39a6b967a45e02"))
    )
    (comp (ref "FB5")
      (value "742792641")
      (footprint "FP-742792641-MFG")
      (description "FERRITE BEAD 300 OHM 0603 1LN")
      (fields (field (name "TOLERANCE") "25%"))
      (libsource (lib "Altium Content Vault") (part "5f30dd21d616792df468990f7003faa"))
    )
    (comp (ref "L2")
      (value "742792780")
      (footprint "SMD-0402")
      (description "SMD EMI Suppression Ferrite Bead WE-CBF, Z = 220 Ohm")
      (libsource (lib "Altium Content Vault") (part "PAS-IND-INDUCTOR-2"))
    )
    (comp (ref "L3")
      (value "742792780")
      (footprint "SMD-0402")
      (description "SMD EMI Suppression Ferrite Bead WE-CBF, Z = 220 Ohm")
      (libsource (lib "Altium Content Vault") (part "PAS-IND-INDUCTOR-2"))
    )
    (comp (ref "L4")
      (value "742792780")
      (footprint "SMD-0402")
      (description "SMD EMI Suppression Ferrite Bead WE-CBF, Z = 220 Ohm")
      (libsource (lib "Altium Content Vault") (part "PAS-IND-INDUCTOR-2"))
    )
    (comp (ref "L5")
      (value "742792780")
      (footprint "SMD-0402")
      (description "SMD EMI Suppression Ferrite Bead WE-CBF, Z = 220 Ohm")
      (libsource (lib "Altium Content Vault") (part "PAS-IND-INDUCTOR-2"))
    )
    (comp (ref "L6")
      (value "742792780")
      (footprint "SMD-0402")
      (description "SMD EMI Suppression Ferrite Bead WE-CBF, Z = 220 Ohm")
      (libsource (lib "Altium Content Vault") (part "PAS-IND-INDUCTOR-2"))
    )
    (comp (ref "L7")
      (value "742792780")
      (footprint "SMD-0402")
      (description "SMD EMI Suppression Ferrite Bead WE-CBF, Z = 220 Ohm")
      (libsource (lib "Altium Content Vault") (part "PAS-IND-INDUCTOR-2"))
    )
    (comp (ref "L8")
      (value "742792780")
      (footprint "SMD-0402")
      (description "SMD EMI Suppression Ferrite Bead WE-CBF, Z = 220 Ohm")
      (libsource (lib "Altium Content Vault") (part "PAS-IND-INDUCTOR-2"))
    )
    (comp (ref "L9")
      (value "742792780")
      (footprint "SMD-0402")
      (description "SMD EMI Suppression Ferrite Bead WE-CBF, Z = 220 Ohm")
      (libsource (lib "Altium Content Vault") (part "PAS-IND-INDUCTOR-2"))
    )
    (comp (ref "L10")
      (value "742792780")
      (footprint "SMD-0402")
      (description "SMD EMI Suppression Ferrite Bead WE-CBF, Z = 220 Ohm")
      (libsource (lib "Altium Content Vault") (part "PAS-IND-INDUCTOR-2"))
    )
    (comp (ref "L11")
      (value "742792780")
      (footprint "SMD-0402")
      (description "SMD EMI Suppression Ferrite Bead WE-CBF, Z = 220 Ohm")
      (libsource (lib "Altium Content Vault") (part "PAS-IND-INDUCTOR-2"))
    )
    (comp (ref "L12")
      (value "742792780")
      (footprint "SMD-0402")
      (description "SMD EMI Suppression Ferrite Bead WE-CBF, Z = 220 Ohm")
      (libsource (lib "Altium Content Vault") (part "PAS-IND-INDUCTOR-2"))
    )
    (comp (ref "L13")
      (value "742792780")
      (footprint "SMD-0402")
      (description "SMD EMI Suppression Ferrite Bead WE-CBF, Z = 220 Ohm")
      (libsource (lib "Altium Content Vault") (part "PAS-IND-INDUCTOR-2"))
    )
    (comp (ref "L14")
      (value "742792780")
      (footprint "SMD-0402")
      (description "SMD EMI Suppression Ferrite Bead WE-CBF, Z = 220 Ohm")
      (libsource (lib "Altium Content Vault") (part "PAS-IND-INDUCTOR-2"))
    )
    (comp (ref "L15")
      (value "742792780")
      (footprint "SMD-0402")
      (description "SMD EMI Suppression Ferrite Bead WE-CBF, Z = 220 Ohm")
      (libsource (lib "Altium Content Vault") (part "PAS-IND-INDUCTOR-2"))
    )
    (comp (ref "L16")
      (value "742792780")
      (footprint "SMD-0402")
      (description "SMD EMI Suppression Ferrite Bead WE-CBF, Z = 220 Ohm")
      (libsource (lib "Altium Content Vault") (part "PAS-IND-INDUCTOR-2"))
    )
    (comp (ref "L17")
      (value "742792780")
      (footprint "SMD-0402")
      (description "SMD EMI Suppression Ferrite Bead WE-CBF, Z = 220 Ohm")
      (libsource (lib "Altium Content Vault") (part "PAS-IND-INDUCTOR-2"))
    )
    (comp (ref "L18")
      (value "742792780")
      (footprint "SMD-0402")
      (description "SMD EMI Suppression Ferrite Bead WE-CBF, Z = 220 Ohm")
      (libsource (lib "Altium Content Vault") (part "PAS-IND-INDUCTOR-2"))
    )
    (comp (ref "L19")
      (value "742792780")
      (footprint "SMD-0402")
      (description "SMD EMI Suppression Ferrite Bead WE-CBF, Z = 220 Ohm")
      (libsource (lib "Altium Content Vault") (part "PAS-IND-INDUCTOR-2"))
    )
    (comp (ref "L21")
      (value "742792780")
      (footprint "SMD-0402")
      (description "SMD EMI Suppression Ferrite Bead WE-CBF, Z = 220 Ohm")
      (libsource (lib "Altium Content Vault") (part "PAS-IND-INDUCTOR-2"))
    )
    (comp (ref "L22")
      (value "742792780")
      (footprint "SMD-0402")
      (description "SMD EMI Suppression Ferrite Bead WE-CBF, Z = 220 Ohm")
      (libsource (lib "Altium Content Vault") (part "PAS-IND-INDUCTOR-2"))
    )
    (comp (ref "L23")
      (value "742792780")
      (footprint "SMD-0402")
      (description "SMD EMI Suppression Ferrite Bead WE-CBF, Z = 220 Ohm")
      (libsource (lib "Altium Content Vault") (part "PAS-IND-INDUCTOR-2"))
    )
    (comp (ref "L24")
      (value "742792780")
      (footprint "SMD-0402")
      (description "SMD EMI Suppression Ferrite Bead WE-CBF, Z = 220 Ohm")
      (libsource (lib "Altium Content Vault") (part "PAS-IND-INDUCTOR-2"))
    )
    (comp (ref "L25")
      (value "742792780")
      (footprint "SMD-0402")
      (description "SMD EMI Suppression Ferrite Bead WE-CBF, Z = 220 Ohm")
      (libsource (lib "Altium Content Vault") (part "PAS-IND-INDUCTOR-2"))
    )
    (comp (ref "L26")
      (value "742792780")
      (footprint "SMD-0402")
      (description "SMD EMI Suppression Ferrite Bead WE-CBF, Z = 220 Ohm")
      (libsource (lib "Altium Content Vault") (part "PAS-IND-INDUCTOR-2"))
    )
    (comp (ref "L27")
      (value "742792780")
      (footprint "SMD-0402")
      (description "SMD EMI Suppression Ferrite Bead WE-CBF, Z = 220 Ohm")
      (libsource (lib "Altium Content Vault") (part "PAS-IND-INDUCTOR-2"))
    )
    (comp (ref "L28")
      (value "742792780")
      (footprint "SMD-0402")
      (description "SMD EMI Suppression Ferrite Bead WE-CBF, Z = 220 Ohm")
      (libsource (lib "Altium Content Vault") (part "PAS-IND-INDUCTOR-2"))
    )
    (comp (ref "L29")
      (value "742792780")
      (footprint "SMD-0402")
      (description "SMD EMI Suppression Ferrite Bead WE-CBF, Z = 220 Ohm")
      (libsource (lib "Altium Content Vault") (part "PAS-IND-INDUCTOR-2"))
    )
    (comp (ref "L30")
      (value "742792780")
      (footprint "SMD-0402")
      (description "SMD EMI Suppression Ferrite Bead WE-CBF, Z = 220 Ohm")
      (libsource (lib "Altium Content Vault") (part "PAS-IND-INDUCTOR-2"))
    )
    (comp (ref "R62")
      (value "DNI_0_5%_0402")
      (footprint "FP-AC0402-0_37-IPC_B")
      (description "RESISTOR 0402 JUMPER ZERO OHM")
      (fields (field (name "TOLERANCE") "1%"))
      (libsource (lib "Altium Content Vault") (part "1029c3af85768c4190bb7ad29bc67b5"))
    )
    (comp (ref "R79")
      (value "0_5%_0402")
      (footprint "RESC1005X40X25LL10T10")
      (fields (field (name "MANUFACTURER") "KOA Speer") (field (name "PART NUMBER") "RK73Z1ETTP"))
      (libsource (lib "Altium Content Vault") (part "RES"))
    )
    (comp (ref "R80")
      (value "0_5%_0402")
      (footprint "RESC1005X40X25LL10T10")
      (fields (field (name "MANUFACTURER") "KOA Speer") (field (name "PART NUMBER") "RK73Z1ETTP"))
      (libsource (lib "Altium Content Vault") (part "RES"))
    )
    (comp (ref "R81")
      (value "0_5%_0402")
      (footprint "FP-AC0402-0_37-IPC_B")
      (description "RESISTOR 0402 JUMPER ZERO OHM")
      (fields (field (name "TOLERANCE") "1%"))
      (libsource (lib "Altium Content Vault") (part "1029c3af85768c4190bb7ad29bc67b5"))
    )
    (comp (ref "R82")
      (value "4.7K_1%_0402")
      (footprint "RESC1005X40X25NL10T10")
      (fields (field (name "MANUFACTURER") "Bourns") (field (name "PART NUMBER") "CR0402-FX-4701GLF"))
      (libsource (lib "Altium Content Vault") (part "RES"))
    )
    (comp (ref "R83")
      (value "4.7K_1%_0402")
      (footprint "RESC1005X40X25NL10T10")
      (fields (field (name "MANUFACTURER") "Bourns") (field (name "PART NUMBER") "CR0402-FX-4701GLF"))
      (libsource (lib "Altium Content Vault") (part "RES"))
    )
    (comp (ref "R84")
      (value "4.7K_1%_0402")
      (footprint "RESC1005X40X25NL10T10")
      (fields (field (name "MANUFACTURER") "Bourns") (field (name "PART NUMBER") "CR0402-FX-4701GLF"))
      (libsource (lib "Altium Content Vault") (part "RES"))
    )
    (comp (ref "R87")
      (value "100_1%_0402")
      (footprint "RESC1005X40X25ML05T10")
      (fields (field (name "PART NUMBER") "ERJ-U02F1000X") (field (name "MANUFACTURER") "Panasonic"))
      (libsource (lib "Altium Content Vault") (part "RES"))
    )
    (comp (ref "R88")
      (value "49.9_1%_0402")
      (footprint "RESC1005X40X25NL10T10")
      (fields (field (name "PART NUMBER") "RK73H1ETTP49R9F") (field (name "MANUFACTURER") "KOA Speer"))
      (libsource (lib "Altium Content Vault") (part "RES"))
    )
    (comp (ref "R89")
      (value "100_1%_0402")
      (footprint "RESC1005X40X25ML05T10")
      (fields (field (name "PART NUMBER") "ERJ-U02F1000X") (field (name "MANUFACTURER") "Panasonic"))
      (libsource (lib "Altium Content Vault") (part "RES"))
    )
    (comp (ref "R210")
      (value "100_1%_0402")
      (footprint "RESC1005X40X25ML05T10")
      (fields (field (name "PART NUMBER") "ERJ-U02F1000X") (field (name "MANUFACTURER") "Panasonic"))
      (libsource (lib "Altium Content Vault") (part "RES"))
    )
    (comp (ref "R212")
      (value "100_1%_0402")
      (footprint "RESC1005X40X25ML05T10")
      (fields (field (name "PART NUMBER") "ERJ-U02F1000X") (field (name "MANUFACTURER") "Panasonic"))
      (libsource (lib "Altium Content Vault") (part "RES"))
    )
    (comp (ref "R246")
      (value "49.9_1%_0402")
      (footprint "RESC1005X40X25NL10T10")
      (fields (field (name "PART NUMBER") "RK73H1ETTP49R9F") (field (name "MANUFACTURER") "KOA Speer"))
      (libsource (lib "Altium Content Vault") (part "RES"))
    )
    (comp (ref "Y2")
      (value "SiTime_SiT5501AC-WU-33E0-10T")
      (footprint "SITIME_SPL-086-CQFN-010-C07050_REV_DRAFT")
      (description "OSC, MEMS, STRATUM 3E, 10.000MHZ, 10PPB STAB, LVCMOS, 3.3V, O/P EN, 7.0X5.0X2.2MM, CQFN-10")
      (fields
        (field (name "MANUFACTURER PART NUMBER") "SiT5501AI-WU033JH-10.000000")
        (field (name "MANUFACTURER") "SiTime")
      )
      (libsource (lib "OCXO_DaughterCard") (part "CMP-OSC-00029-2"))
    )
    (comp (ref "Y3")
      (value "DNI_ASEMPC-40.000MHZ-XR-T")
      (footprint "FP-ASEMP-CMOS-MFG")
      (description "MEMS Oscillator 40MHz ±25ppm CMOS 2.25V~3.6V 6-SMD 3.2mm x 2.5mm")
      (libsource (lib "Altium Content Vault") (part "9526c112e3a98a1af86e8f4e974a861"))
    )
    (comp (ref "Y4")
      (value "SIT5001AC-3E-33N0-40.000000X")
      (footprint "FP-SiT5001-3-MFG")
      (description "MEMS OSC TCXO 40.0000MHZ LVCMOS")
      (libsource (lib "Altium Content Vault") (part "f2b4964c30f19ad016f2c5313c7e3e3"))
    )
    (comp (ref "Y6")
      (value "DNI_TWETMCJANF-10.000000")
      (footprint "FP-TWETMCJANF-10_000000-MFG")
      (description "XTAL OSC TCXO 10.0000MHZ CMOS")
      (fields
        (field (name "MANUFACTURER PART NUMBER") "TWETMCJANF-10.000000")
        (field (name "OCTOPART") "https://octopart.com/twetmcjanf-10.000000-taitien-75080612")
      )
      (libsource (lib "Altium Content Vault") (part "cad4c3239b6ef19b17a0f879cedd8e8"))
    )
  )
  (nets
    (net (code "1") (name "DPLL_OSCI") (class "Default")
      (node (ref "C152") (pin "2") (pinfunction "2_2") (pintype "passive"))
      (node (ref "C278") (pin "2") (pinfunction "2_2") (pintype "passive"))
    )
    (net (code "2") (name "DPLL_VDDA_BG_LC") (class "Default")
      (node (ref "C83") (pin "1") (pinfunction "1_1") (pintype "passive"))
      (node (ref "C84") (pin "1") (pinfunction "1_1") (pintype "passive"))
      (node (ref "C85") (pin "1") (pinfunction "1_1") (pintype "passive"))
      (node (ref "L2") (pin "2") (pinfunction "2_2") (pintype "passive"))
    )
    (net (code "3") (name "DPLL_VDDA_FB") (class "Default")
      (node (ref "C125") (pin "1") (pinfunction "1_1") (pintype "passive"))
      (node (ref "C126") (pin "1") (pinfunction "1_1") (pintype "passive"))
      (node (ref "L13") (pin "2") (pinfunction "2_2") (pintype "passive"))
    )
    (net (code "4") (name "DPLL_VDDA_PDCP_XTAL") (class "Default")
      (node (ref "C100") (pin "1") (pinfunction "1_1") (pintype "passive"))
      (node (ref "C99") (pin "1") (pinfunction "1_1") (pintype "passive"))
      (node (ref "L5") (pin "2") (pinfunction "2_2") (pintype "passive"))
    )
    (net (code "5") (name "DPLL_VDDO_Q0") (class "Default")
      (node (ref "C111") (pin "1") (pinfunction "1_1") (pintype "passive"))
      (node (ref "C112") (pin "1") (pinfunction "1_1") (pintype "passive"))
      (node (ref "L8") (pin "2") (pinfunction "2_2") (pintype "passive"))
    )
    (net (code "6") (name "DPLL_VDDO_Q1") (class "Default")
      (node (ref "C127") (pin "1") (pinfunction "1_1") (pintype "passive"))
      (node (ref "C128") (pin "1") (pinfunction "1_1") (pintype "passive"))
      (node (ref "L12") (pin "2") (pinfunction "2_2") (pintype "passive"))
    )
    (net (code "7") (name "DPLL_VDDO_Q2") (class "Default")
      (node (ref "C139") (pin "1") (pinfunction "1_1") (pintype "passive"))
      (node (ref "C140") (pin "1") (pinfunction "1_1") (pintype "passive"))
      (node (ref "L16") (pin "2") (pinfunction "2_2") (pintype "passive"))
    )
    (net (code "8") (name "DPLL_VDDO_Q3") (class "Default")
      (node (ref "C148") (pin "1") (pinfunction "1_1") (pintype "passive"))
      (node (ref "C149") (pin "1") (pinfunction "1_1") (pintype "passive"))
      (node (ref "L18") (pin "2") (pinfunction "2_2") (pintype "passive"))
    )
    (net (code "9") (name "DPLL_VDDO_Q4") (class "Default")
      (node (ref "C106") (pin "1") (pinfunction "1_1") (pintype "passive"))
      (node (ref "C107") (pin "1") (pinfunction "1_1") (pintype "passive"))
      (node (ref "L7") (pin "2") (pinfunction "2_2") (pintype "passive"))
    )
    (net (code "10") (name "DPLL_VDDO_Q5") (class "Default")
      (node (ref "C118") (pin "1") (pinfunction "1_1") (pintype "passive"))
      (node (ref "C119") (pin "1") (pinfunction "1_1") (pintype "passive"))
      (node (ref "L10") (pin "2") (pinfunction "2_2") (pintype "passive"))
    )
    (net (code "11") (name "DPLL_VDDO_Q6") (class "Default")
      (node (ref "C132") (pin "1") (pinfunction "1_1") (pintype "passive"))
      (node (ref "C133") (pin "1") (pinfunction "1_1") (pintype "passive"))
      (node (ref "L14") (pin "2") (pinfunction "2_2") (pintype "passive"))
    )
    (net (code "12") (name "DPLL_VDDO_Q7") (class "Default")
      (node (ref "C143") (pin "1") (pinfunction "1_1") (pintype "passive"))
      (node (ref "C144") (pin "1") (pinfunction "1_1") (pintype "passive"))
      (node (ref "L17") (pin "2") (pinfunction "2_2") (pintype "passive"))
    )
    (net (code "13") (name "DPLL_VDDO_Q8") (class "Default")
      (node (ref "C264") (pin "1") (pinfunction "1_1") (pintype "passive"))
      (node (ref "C265") (pin "1") (pinfunction "1_1") (pintype "passive"))
      (node (ref "L27") (pin "2") (pinfunction "2_2") (pintype "passive"))
    )
    (net (code "14") (name "DPLL_VDDO_Q9") (class "Default")
      (node (ref "C268") (pin "1") (pinfunction "1_1") (pintype "passive"))
      (node (ref "C269") (pin "1") (pinfunction "1_1") (pintype "passive"))
      (node (ref "L28") (pin "2") (pinfunction "2_2") (pintype "passive"))
    )
    (net (code "15") (name "DPLL_VDDO_Q10") (class "Default")
      (node (ref "C276") (pin "1") (pinfunction "1_1") (pintype "passive"))
      (node (ref "C277") (pin "1") (pinfunction "1_1") (pintype "passive"))
      (node (ref "L30") (pin "2") (pinfunction "2_2") (pintype "passive"))
    )
    (net (code "16") (name "DPLL_VDDO_Q11") (class "Default")
      (node (ref "C274") (pin "1") (pinfunction "1_1") (pintype "passive"))
      (node (ref "C275") (pin "1") (pinfunction "1_1") (pintype "passive"))
      (node (ref "L29") (pin "2") (pinfunction "2_2") (pintype "passive"))
    )
    (net (code "17") (name "DPLL_VDD_CLKA") (class "Default")
      (node (ref "C134") (pin "1") (pinfunction "1_1") (pintype "passive"))
      (node (ref "C135") (pin "1") (pinfunction "1_1") (pintype "passive"))
      (node (ref "L15") (pin "2") (pinfunction "2_2") (pintype "passive"))
    )
    (net (code "18") (name "DPLL_VDD_CLKB") (class "Default")
      (node (ref "C120") (pin "1") (pinfunction "1_1") (pintype "passive"))
      (node (ref "C121") (pin "1") (pinfunction "1_1") (pintype "passive"))
      (node (ref "L11") (pin "2") (pinfunction "2_2") (pintype "passive"))
    )
    (net (code "19") (name "DPLL_VDD_DCO_Q01") (class "Default")
      (node (ref "C102") (pin "1") (pinfunction "1_1") (pintype "passive"))
      (node (ref "C103") (pin "1") (pinfunction "1_1") (pintype "passive"))
      (node (ref "L6") (pin "2") (pinfunction "2_2") (pintype "passive"))
    )
    (net (code "20") (name "DPLL_VDD_DCO_Q8") (class "Default")
      (node (ref "C250") (pin "1") (pinfunction "1_1") (pintype "passive"))
      (node (ref "C251") (pin "1") (pinfunction "1_1") (pintype "passive"))
      (node (ref "L23") (pin "2") (pinfunction "2_2") (pintype "passive"))
    )
    (net (code "21") (name "DPLL_VDD_DCO_Q9") (class "Default")
      (node (ref "C253") (pin "1") (pinfunction "1_1") (pintype "passive"))
      (node (ref "C254") (pin "1") (pinfunction "1_1") (pintype "passive"))
      (node (ref "L24") (pin "2") (pinfunction "2_2") (pintype "passive"))
    )
    (net (code "22") (name "DPLL_VDD_DCO_Q10") (class "Default")
      (node (ref "C256") (pin "1") (pinfunction "1_1") (pintype "passive"))
      (node (ref "C257") (pin "1") (pinfunction "1_1") (pintype "passive"))
      (node (ref "L25") (pin "2") (pinfunction "2_2") (pintype "passive"))
    )
    (net (code "23") (name "DPLL_VDD_DCO_Q11") (class "Default")
      (node (ref "C259") (pin "1") (pinfunction "1_1") (pintype "passive"))
      (node (ref "C260") (pin "1") (pinfunction "1_1") (pintype "passive"))
      (node (ref "L26") (pin "2") (pinfunction "2_2") (pintype "passive"))
    )
    (net (code "24") (name "DPLL_VDD_DCO_Q23") (class "Default")
      (node (ref "C113") (pin "1") (pinfunction "1_1") (pintype "passive"))
      (node (ref "C114") (pin "1") (pinfunction "1_1") (pintype "passive"))
      (node (ref "L9") (pin "2") (pinfunction "2_2") (pintype "passive"))
    )
    (net (code "25") (name "DPLL_VDD_DCO_Q45") (class "Default")
      (node (ref "C242") (pin "1") (pinfunction "1_1") (pintype "passive"))
      (node (ref "C243") (pin "1") (pinfunction "1_1") (pintype "passive"))
      (node (ref "L21") (pin "2") (pinfunction "2_2") (pintype "passive"))
    )
    (net (code "26") (name "DPLL_VDD_DCO_Q67") (class "Default")
      (node (ref "C247") (pin "1") (pinfunction "1_1") (pintype "passive"))
      (node (ref "C248") (pin "1") (pinfunction "1_1") (pintype "passive"))
      (node (ref "L22") (pin "2") (pinfunction "2_2") (pintype "passive"))
    )
    (net (code "27") (name "DPLL_VDD_DIA_A") (class "Default")
      (node (ref "C77") (pin "1") (pinfunction "1_1") (pintype "passive"))
      (node (ref "C78") (pin "1") (pinfunction "1_1") (pintype "passive"))
      (node (ref "L3") (pin "2") (pinfunction "2_2") (pintype "passive"))
    )
    (net (code "28") (name "DPLL_VDD_DIA_B") (class "Default")
      (node (ref "C92") (pin "1") (pinfunction "1_1") (pintype "passive"))
      (node (ref "C93") (pin "1") (pinfunction "1_1") (pintype "passive"))
      (node (ref "L4") (pin "2") (pinfunction "2_2") (pintype "passive"))
    )
    (net (code "29") (name "DPLL_VDD_DIG") (class "Default")
      (node (ref "C79") (pin "1") (pinfunction "1_1") (pintype "passive"))
      (node (ref "C80") (pin "1") (pinfunction "1_1") (pintype "passive"))
      (node (ref "C81") (pin "1") (pinfunction "1_1") (pintype "passive"))
      (node (ref "C82") (pin "1") (pinfunction "1_1") (pintype "passive"))
      (node (ref "R79") (pin "2") (pinfunction "2_2") (pintype "passive"))
    )
    (net (code "30") (name "DPLL_VDD_GPIO") (class "Default")
      (node (ref "C95") (pin "1") (pinfunction "1_1") (pintype "passive"))
      (node (ref "C96") (pin "1") (pinfunction "1_1") (pintype "passive"))
      (node (ref "C97") (pin "1") (pinfunction "1_1") (pintype "passive"))
      (node (ref "C98") (pin "1") (pinfunction "1_1") (pintype "passive"))
      (node (ref "R80") (pin "2") (pinfunction "2_2") (pintype "passive"))
    )
    (net (code "31") (name "DPLL_XO") (class "Default")
      (node (ref "R62") (pin "1") (pinfunction "1_1") (pintype "passive"))
      (node (ref "R81") (pin "1") (pinfunction "1_1") (pintype "passive"))
    )
    (net (code "32") (name "GND") (class "Default")
      (node (ref "C100") (pin "2") (pinfunction "2_2") (pintype "passive"))
      (node (ref "C101") (pin "2") (pinfunction "2_2") (pintype "passive"))
      (node (ref "C102") (pin "2") (pinfunction "2_2") (pintype "passive"))
      (node (ref "C103") (pin "2") (pinfunction "2_2") (pintype "passive"))
      (node (ref "C104") (pin "2") (pinfunction "2_2") (pintype "passive"))
      (node (ref "C105") (pin "2") (pinfunction "2_2") (pintype "passive"))
      (node (ref "C106") (pin "2") (pinfunction "2_2") (pintype "passive"))
      (node (ref "C107") (pin "2") (pinfunction "2_2") (pintype "passive"))
      (node (ref "C108") (pin "2") (pinfunction "2_2") (pintype "passive"))
      (node (ref "C109") (pin "2") (pinfunction "2_2") (pintype "passive"))
      (node (ref "C110") (pin "2") (pinfunction "2_2") (pintype "passive"))
      (node (ref "C111") (pin "2") (pinfunction "2_2") (pintype "passive"))
      (node (ref "C112") (pin "2") (pinfunction "2_2") (pintype "passive"))
      (node (ref "C113") (pin "2") (pinfunction "2_2") (pintype "passive"))
      (node (ref "C114") (pin "2") (pinfunction "2_2") (pintype "passive"))
      (node (ref "C115") (pin "2") (pinfunction "2_2") (pintype "passive"))
      (node (ref "C116") (pin "2") (pinfunction "2_2") (pintype "passive"))
      (node (ref "C117") (pin "2") (pinfunction "2_2") (pintype "passive"))
      (node (ref "C118") (pin "2") (pinfunction "2_2") (pintype "passive"))
      (node (ref "C119") (pin "2") (pinfunction "2_2") (pintype "passive"))
      (node (ref "C120") (pin "2") (pinfunction "2_2") (pintype "passive"))
      (node (ref "C121") (pin "2") (pinfunction "2_2") (pintype "passive"))
      (node (ref "C122") (pin "2") (pinfunction "2_2") (pintype "passive"))
      (node (ref "C123") (pin "2") (pinfunction "2_2") (pintype "passive"))
      (node (ref "C124") (pin "2") (pinfunction "2_2") (pintype "passive"))
      (node (ref "C125") (pin "2") (pinfunction "2_2") (pintype "passive"))
      (node (ref "C126") (pin "2") (pinfunction "2_2") (pintype "passive"))
      (node (ref "C127") (pin "2") (pinfunction "2_2") (pintype "passive"))
      (node (ref "C128") (pin "2") (pinfunction "2_2") (pintype "passive"))
      (node (ref "C129") (pin "2") (pinfunction "2_2") (pintype "passive"))
      (node (ref "C130") (pin "2") (pinfunction "2_2") (pintype "passive"))
      (node (ref "C131") (pin "2") (pinfunction "2_2") (pintype "passive"))
      (node (ref "C132") (pin "2") (pinfunction "2_2") (pintype "passive"))
      (node (ref "C133") (pin "2") (pinfunction "2_2") (pintype "passive"))
      (node (ref "C134") (pin "2") (pinfunction "2_2") (pintype "passive"))
      (node (ref "C135") (pin "2") (pinfunction "2_2") (pintype "passive"))
      (node (ref "C136") (pin "2") (pinfunction "2_2") (pintype "passive"))
      (node (ref "C137") (pin "2") (pinfunction "2_2") (pintype "passive"))
      (node (ref "C138") (pin "2") (pinfunction "2_2") (pintype "passive"))
      (node (ref "C139") (pin "2") (pinfunction "2_2") (pintype "passive"))
      (node (ref "C140") (pin "2") (pinfunction "2_2") (pintype "passive"))
      (node (ref "C141") (pin "2") (pinfunction "2_2") (pintype "passive"))
      (node (ref "C142") (pin "2") (pinfunction "2_2") (pintype "passive"))
      (node (ref "C143") (pin "2") (pinfunction "2_2") (pintype "passive"))
      (node (ref "C144") (pin "2") (pinfunction "2_2") (pintype "passive"))
      (node (ref "C145") (pin "1") (pinfunction "1_1") (pintype "passive"))
      (node (ref "C146") (pin "2") (pinfunction "2_2") (pintype "passive"))
      (node (ref "C147") (pin "2") (pinfunction "2_2") (pintype "passive"))
      (node (ref "C148") (pin "2") (pinfunction "2_2") (pintype "passive"))
      (node (ref "C149") (pin "2") (pinfunction "2_2") (pintype "passive"))
      (node (ref "C150") (pin "2") (pinfunction "2_2") (pintype "passive"))
      (node (ref "C151") (pin "1") (pinfunction "1_1") (pintype "passive"))
      (node (ref "C153") (pin "2") (pinfunction "2_2") (pintype "passive"))
      (node (ref "C154") (pin "2") (pinfunction "2_2") (pintype "passive"))
      (node (ref "C155") (pin "2") (pinfunction "2_2") (pintype "passive"))
      (node (ref "C156") (pin "2") (pinfunction "2_2") (pintype "passive"))
      (node (ref "C242") (pin "2") (pinfunction "2_2") (pintype "passive"))
      (node (ref "C243") (pin "2") (pinfunction "2_2") (pintype "passive"))
      (node (ref "C244") (pin "2") (pinfunction "2_2") (pintype "passive"))
      (node (ref "C245") (pin "2") (pinfunction "2_2") (pintype "passive"))
      (node (ref "C246") (pin "2") (pinfunction "2_2") (pintype "passive"))
      (node (ref "C247") (pin "2") (pinfunction "2_2") (pintype "passive"))
      (node (ref "C248") (pin "2") (pinfunction "2_2") (pintype "passive"))
      (node (ref "C249") (pin "2") (pinfunction "2_2") (pintype "passive"))
      (node (ref "C250") (pin "2") (pinfunction "2_2") (pintype "passive"))
      (node (ref "C251") (pin "2") (pinfunction "2_2") (pintype "passive"))
      (node (ref "C252") (pin "2") (pinfunction "2_2") (pintype "passive"))
      (node (ref "C253") (pin "2") (pinfunction "2_2") (pintype "passive"))
      (node (ref "C254") (pin "2") (pinfunction "2_2") (pintype "passive"))
      (node (ref "C255") (pin "2") (pinfunction "2_2") (pintype "passive"))
      (node (ref "C256") (pin "2") (pinfunction "2_2") (pintype "passive"))
      (node (ref "C257") (pin "2") (pinfunction "2_2") (pintype "passive"))
      (node (ref "C258") (pin "2") (pinfunction "2_2") (pintype "passive"))
      (node (ref "C259") (pin "2") (pinfunction "2_2") (pintype "passive"))
      (node (ref "C260") (pin "2") (pinfunction "2_2") (pintype "passive"))
      (node (ref "C261") (pin "2") (pinfunction "2_2") (pintype "passive"))
      (node (ref "C262") (pin "2") (pinfunction "2_2") (pintype "passive"))
      (node (ref "C263") (pin "2") (pinfunction "2_2") (pintype "passive"))
      (node (ref "C264") (pin "2") (pinfunction "2_2") (pintype "passive"))
      (node (ref "C265") (pin "2") (pinfunction "2_2") (pintype "passive"))
      (node (ref "C266") (pin "2") (pinfunction "2_2") (pintype "passive"))
      (node (ref "C267") (pin "2") (pinfunction "2_2") (pintype "passive"))
      (node (ref "C268") (pin "2") (pinfunction "2_2") (pintype "passive"))
      (node (ref "C269") (pin "2") (pinfunction "2_2") (pintype "passive"))
      (node (ref "C270") (pin "2") (pinfunction "2_2") (pintype "passive"))
      (node (ref "C271") (pin "2") (pinfunction "2_2") (pintype "passive"))
      (node (ref "C272") (pin "2") (pinfunction "2_2") (pintype "passive"))
      (node (ref "C273") (pin "2") (pinfunction "2_2") (pintype "passive"))
      (node (ref "C274") (pin "2") (pinfunction "2_2") (pintype "passive"))
      (node (ref "C275") (pin "2") (pinfunction "2_2") (pintype "passive"))
      (node (ref "C276") (pin "2") (pinfunction "2_2") (pintype "passive"))
      (node (ref "C277") (pin "2") (pinfunction "2_2") (pintype "passive"))
      (node (ref "C281") (pin "2") (pinfunction "2_2") (pintype "passive"))
      (node (ref "C282") (pin "2") (pinfunction "2_2") (pintype "passive"))
      (node (ref "C77") (pin "2") (pinfunction "2_2") (pintype "passive"))
      (node (ref "C78") (pin "2") (pinfunction "2_2") (pintype "passive"))
      (node (ref "C79") (pin "2") (pinfunction "2_2") (pintype "passive"))
      (node (ref "C80") (pin "2") (pinfunction "2_2") (pintype "passive"))
      (node (ref "C81") (pin "2") (pinfunction "2_2") (pintype "passive"))
      (node (ref "C82") (pin "2") (pinfunction "2_2") (pintype "passive"))
      (node (ref "C83") (pin "2") (pinfunction "2_2") (pintype "passive"))
      (node (ref "C84") (pin "2") (pinfunction "2_2") (pintype "passive"))
      (node (ref "C85") (pin "2") (pinfunction "2_2") (pintype "passive"))
      (node (ref "C86") (pin "2") (pinfunction "2_2") (pintype "passive"))
      (node (ref "C87") (pin "2") (pinfunction "2_2") (pintype "passive"))
      (node (ref "C88") (pin "2") (pinfunction "2_2") (pintype "passive"))
      (node (ref "C89") (pin "2") (pinfunction "2_2") (pintype "passive"))
      (node (ref "C90") (pin "2") (pinfunction "2_2") (pintype "passive"))
      (node (ref "C91") (pin "2") (pinfunction "2_2") (pintype "passive"))
      (node (ref "C92") (pin "2") (pinfunction "2_2") (pintype "passive"))
      (node (ref "C93") (pin "2") (pinfunction "2_2") (pintype "passive"))
      (node (ref "C94") (pin "2") (pinfunction "2_2") (pintype "passive"))
      (node (ref "C95") (pin "2") (pinfunction "2_2") (pintype "passive"))
      (node (ref "C96") (pin "2") (pinfunction "2_2") (pintype "passive"))
      (node (ref "C97") (pin "2") (pinfunction "2_2") (pintype "passive"))
      (node (ref "C98") (pin "2") (pinfunction "2_2") (pintype "passive"))
      (node (ref "C99") (pin "2") (pinfunction "2_2") (pintype "passive"))
      (node (ref "R212") (pin "1") (pinfunction "1_1") (pintype "passive"))
      (node (ref "R89") (pin "1") (pinfunction "1_1") (pintype "passive"))
      (node (ref "Y2") (pin "5") (pinfunction "GND_5") (pintype "power_in"))
      (node (ref "Y3") (pin "3") (pinfunction "GND_3") (pintype "power_in"))
      (node (ref "Y4") (pin "2") (pinfunction "GND_2") (pintype "power_in"))
      (node (ref "Y6") (pin "1") (pinfunction "GND/NC_1") (pintype "passive"))
      (node (ref "Y6") (pin "2") (pinfunction "GND_2") (pintype "power_in"))
    )
    (net (code "33") (name "Net-(C152-Pad1)") (class "Default")
      (node (ref "C152") (pin "1") (pinfunction "1_1") (pintype "passive"))
      (node (ref "R87") (pin "1") (pinfunction "1_1") (pintype "passive"))
      (node (ref "R88") (pin "2") (pinfunction "2_2") (pintype "passive"))
      (node (ref "R89") (pin "2") (pinfunction "2_2") (pintype "passive"))
    )
    (net (code "34") (name "Net-(C278-Pad1)") (class "Default")
      (node (ref "C278") (pin "1") (pinfunction "1_1") (pintype "passive"))
      (node (ref "R210") (pin "1") (pinfunction "1_1") (pintype "passive"))
      (node (ref "R212") (pin "2") (pinfunction "2_2") (pintype "passive"))
      (node (ref "R246") (pin "2") (pinfunction "2_2") (pintype "passive"))
    )
    (net (code "35") (name "Net-(R83-Pad1)") (class "Default")
      (node (ref "R83") (pin "1") (pinfunction "1_1") (pintype "passive"))
      (node (ref "Y2") (pin "7") (pinfunction "NC_7") (pintype "passive"))
    )
    (net (code "36") (name "Net-(R84-Pad1)") (class "Default")
      (node (ref "R84") (pin "1") (pinfunction "1_1") (pintype "passive"))
      (node (ref "Y2") (pin "8") (pinfunction "NC_8") (pintype "passive"))
    )
    (net (code "37") (name "Net-(Y2-CLK)") (class "Default")
      (node (ref "R81") (pin "2") (pinfunction "2_2") (pintype "passive"))
      (node (ref "Y2") (pin "6") (pinfunction "CLK_6") (pintype "output"))
    )
    (net (code "38") (name "Net-(Y2-OE)") (class "Default")
      (node (ref "R82") (pin "2") (pinfunction "2_2") (pintype "passive"))
      (node (ref "Y2") (pin "1") (pinfunction "OE_1") (pintype "input"))
    )
    (net (code "39") (name "Net-(Y2-VDD)") (class "Default")
      (node (ref "C150") (pin "1") (pinfunction "1_1") (pintype "passive"))
      (node (ref "C151") (pin "2") (pinfunction "2_2") (pintype "passive"))
      (node (ref "FB5") (pin "1") (pinfunction "1_1") (pintype "passive"))
      (node (ref "R82") (pin "1") (pinfunction "1_1") (pintype "passive"))
      (node (ref "Y2") (pin "10") (pinfunction "VDD_10") (pintype "power_in"))
      (node (ref "Y6") (pin "4") (pinfunction "VDD_4") (pintype "power_in"))
    )
    (net (code "40") (name "Net-(Y3-Output)") (class "Default")
      (node (ref "R88") (pin "1") (pinfunction "1_1") (pintype "passive"))
      (node (ref "Y3") (pin "4") (pinfunction "Output_4") (pintype "output"))
    )
    (net (code "41") (name "Net-(Y3-VDD)") (class "Default")
      (node (ref "C155") (pin "1") (pinfunction "1_1") (pintype "passive"))
      (node (ref "C156") (pin "1") (pinfunction "1_1") (pintype "passive"))
      (node (ref "C281") (pin "1") (pinfunction "1_1") (pintype "passive"))
      (node (ref "C282") (pin "1") (pinfunction "1_1") (pintype "passive"))
      (node (ref "L19") (pin "2") (pinfunction "2_2") (pintype "passive"))
      (node (ref "Y3") (pin "1") (pinfunction "~{Tri-State}_1") (pintype "input"))
      (node (ref "Y3") (pin "6") (pinfunction "VDD_6") (pintype "power_in"))
      (node (ref "Y4") (pin "4") (pinfunction "VDD_4") (pintype "power_in"))
    )
    (net (code "42") (name "Net-(Y4-OUT)") (class "Default")
      (node (ref "R246") (pin "1") (pinfunction "1_1") (pintype "passive"))
      (node (ref "Y4") (pin "3") (pinfunction "OUT_3") (pintype "output"))
    )
    (net (code "43") (name "Net-(Y6-OUTPUT)") (class "Default")
      (node (ref "R62") (pin "2") (pinfunction "2_2") (pintype "passive"))
      (node (ref "Y6") (pin "3") (pinfunction "OUTPUT_3") (pintype "output"))
    )
    (net (code "44") (name "P1V8") (class "Default")
      (node (ref "C108") (pin "1") (pinfunction "1_1") (pintype "passive"))
      (node (ref "C115") (pin "1") (pinfunction "1_1") (pintype "passive"))
      (node (ref "C129") (pin "1") (pinfunction "1_1") (pintype "passive"))
      (node (ref "C244") (pin "1") (pinfunction "1_1") (pintype "passive"))
      (node (ref "C245") (pin "1") (pinfunction "1_1") (pintype "passive"))
      (node (ref "C246") (pin "1") (pinfunction "1_1") (pintype "passive"))
      (node (ref "C249") (pin "1") (pinfunction "1_1") (pintype "passive"))
      (node (ref "C252") (pin "1") (pinfunction "1_1") (pintype "passive"))
      (node (ref "C255") (pin "1") (pinfunction "1_1") (pintype "passive"))
      (node (ref "C258") (pin "1") (pinfunction "1_1") (pintype "passive"))
      (node (ref "C261") (pin "1") (pinfunction "1_1") (pintype "passive"))
      (node (ref "C88") (pin "1") (pinfunction "1_1") (pintype "passive"))
      (node (ref "C89") (pin "1") (pinfunction "1_1") (pintype "passive"))
      (node (ref "C90") (pin "1") (pinfunction "1_1") (pintype "passive"))
      (node (ref "C94") (pin "1") (pinfunction "1_1") (pintype "passive"))
      (node (ref "L13") (pin "1") (pinfunction "1_1") (pintype "passive"))
      (node (ref "L21") (pin "1") (pinfunction "1_1") (pintype "passive"))
      (node (ref "L22") (pin "1") (pinfunction "1_1") (pintype "passive"))
      (node (ref "L23") (pin "1") (pinfunction "1_1") (pintype "passive"))
      (node (ref "L24") (pin "1") (pinfunction "1_1") (pintype "passive"))
      (node (ref "L25") (pin "1") (pinfunction "1_1") (pintype "passive"))
      (node (ref "L26") (pin "1") (pinfunction "1_1") (pintype "passive"))
      (node (ref "L3") (pin "1") (pinfunction "1_1") (pintype "passive"))
      (node (ref "L4") (pin "1") (pinfunction "1_1") (pintype "passive"))
      (node (ref "L6") (pin "1") (pinfunction "1_1") (pintype "passive"))
      (node (ref "L9") (pin "1") (pinfunction "1_1") (pintype "passive"))
      (node (ref "R79") (pin "1") (pinfunction "1_1") (pintype "passive"))
    )
    (net (code "45") (name "P3V3") (class "Default")
      (node (ref "C101") (pin "1") (pinfunction "1_1") (pintype "passive"))
      (node (ref "C104") (pin "1") (pinfunction "1_1") (pintype "passive"))
      (node (ref "C105") (pin "1") (pinfunction "1_1") (pintype "passive"))
      (node (ref "C109") (pin "1") (pinfunction "1_1") (pintype "passive"))
      (node (ref "C110") (pin "1") (pinfunction "1_1") (pintype "passive"))
      (node (ref "C116") (pin "1") (pinfunction "1_1") (pintype "passive"))
      (node (ref "C117") (pin "1") (pinfunction "1_1") (pintype "passive"))
      (node (ref "C122") (pin "1") (pinfunction "1_1") (pintype "passive"))
      (node (ref "C123") (pin "1") (pinfunction "1_1") (pintype "passive"))
      (node (ref "C124") (pin "1") (pinfunction "1_1") (pintype "passive"))
      (node (ref "C130") (pin "1") (pinfunction "1_1") (pintype "passive"))
      (node (ref "C131") (pin "1") (pinfunction "1_1") (pintype "passive"))
      (node (ref "C136") (pin "1") (pinfunction "1_1") (pintype "passive"))
      (node (ref "C137") (pin "1") (pinfunction "1_1") (pintype "passive"))
      (node (ref "C138") (pin "1") (pinfunction "1_1") (pintype "passive"))
      (node (ref "C141") (pin "1") (pinfunction "1_1") (pintype "passive"))
      (node (ref "C142") (pin "1") (pinfunction "1_1") (pintype "passive"))
      (node (ref "C145") (pin "2") (pinfunction "2_2") (pintype "passive"))
      (node (ref "C146") (pin "1") (pinfunction "1_1") (pintype "passive"))
      (node (ref "C147") (pin "1") (pinfunction "1_1") (pintype "passive"))
      (node (ref "C153") (pin "1") (pinfunction "1_1") (pintype "passive"))
      (node (ref "C154") (pin "1") (pinfunction "1_1") (pintype "passive"))
      (node (ref "C262") (pin "1") (pinfunction "1_1") (pintype "passive"))
      (node (ref "C263") (pin "1") (pinfunction "1_1") (pintype "passive"))
      (node (ref "C266") (pin "1") (pinfunction "1_1") (pintype "passive"))
      (node (ref "C267") (pin "1") (pinfunction "1_1") (pintype "passive"))
      (node (ref "C270") (pin "1") (pinfunction "1_1") (pintype "passive"))
      (node (ref "C271") (pin "1") (pinfunction "1_1") (pintype "passive"))
      (node (ref "C272") (pin "1") (pinfunction "1_1") (pintype "passive"))
      (node (ref "C273") (pin "1") (pinfunction "1_1") (pintype "passive"))
      (node (ref "C86") (pin "1") (pinfunction "1_1") (pintype "passive"))
      (node (ref "C87") (pin "1") (pinfunction "1_1") (pintype "passive"))
      (node (ref "C91") (pin "1") (pinfunction "1_1") (pintype "passive"))
      (node (ref "FB5") (pin "2") (pinfunction "2_2") (pintype "passive"))
      (node (ref "L10") (pin "1") (pinfunction "1_1") (pintype "passive"))
      (node (ref "L11") (pin "1") (pinfunction "1_1") (pintype "passive"))
      (node (ref "L12") (pin "1") (pinfunction "1_1") (pintype "passive"))
      (node (ref "L14") (pin "1") (pinfunction "1_1") (pintype "passive"))
      (node (ref "L15") (pin "1") (pinfunction "1_1") (pintype "passive"))
      (node (ref "L16") (pin "1") (pinfunction "1_1") (pintype "passive"))
      (node (ref "L17") (pin "1") (pinfunction "1_1") (pintype "passive"))
      (node (ref "L18") (pin "1") (pinfunction "1_1") (pintype "passive"))
      (node (ref "L19") (pin "1") (pinfunction "1_1") (pintype "passive"))
      (node (ref "L2") (pin "1") (pinfunction "1_1") (pintype "passive"))
      (node (ref "L27") (pin "1") (pinfunction "1_1") (pintype "passive"))
      (node (ref "L28") (pin "1") (pinfunction "1_1") (pintype "passive"))
      (node (ref "L29") (pin "1") (pinfunction "1_1") (pintype "passive"))
      (node (ref "L30") (pin "1") (pinfunction "1_1") (pintype "passive"))
      (node (ref "L5") (pin "1") (pinfunction "1_1") (pintype "passive"))
      (node (ref "L7") (pin "1") (pinfunction "1_1") (pintype "passive"))
      (node (ref "L8") (pin "1") (pinfunction "1_1") (pintype "passive"))
      (node (ref "R210") (pin "2") (pinfunction "2_2") (pintype "passive"))
      (node (ref "R80") (pin "1") (pinfunction "1_1") (pintype "passive"))
      (node (ref "R83") (pin "2") (pinfunction "2_2") (pintype "passive"))
      (node (ref "R84") (pin "2") (pinfunction "2_2") (pintype "passive"))
      (node (ref "R87") (pin "2") (pinfunction "2_2") (pintype "passive"))
    )
    (net (code "46") (name "TOP_SENS_I2C_SCL") (class "Default")
      (node (ref "Y2") (pin "3") (pinfunction "NC_3") (pintype "passive"))
    )
    (net (code "47") (name "TOP_SENS_I2C_SDA") (class "Default")
      (node (ref "Y2") (pin "2") (pinfunction "NC_2") (pintype "passive"))
    )
    (net (code "48") (name "unconnected-(Y2-NC-Pad4)") (class "Default")
      (node (ref "Y2") (pin "4") (pinfunction "NC_4") (pintype "passive"))
    )
    (net (code "49") (name "unconnected-(Y2-NC-Pad9)") (class "Default")
      (node (ref "Y2") (pin "9") (pinfunction "NC_9") (pintype "passive"))
    )
    (net (code "50") (name "unconnected-(Y4-NC-Pad1)") (class "Default")
      (node (ref "Y4") (pin "1") (pinfunction "NC_1") (pintype "passive"))
    )
  )
)
